# qo-100-lora-transceiver.net
KiCad netlist of a schematic drawn in EAGLE
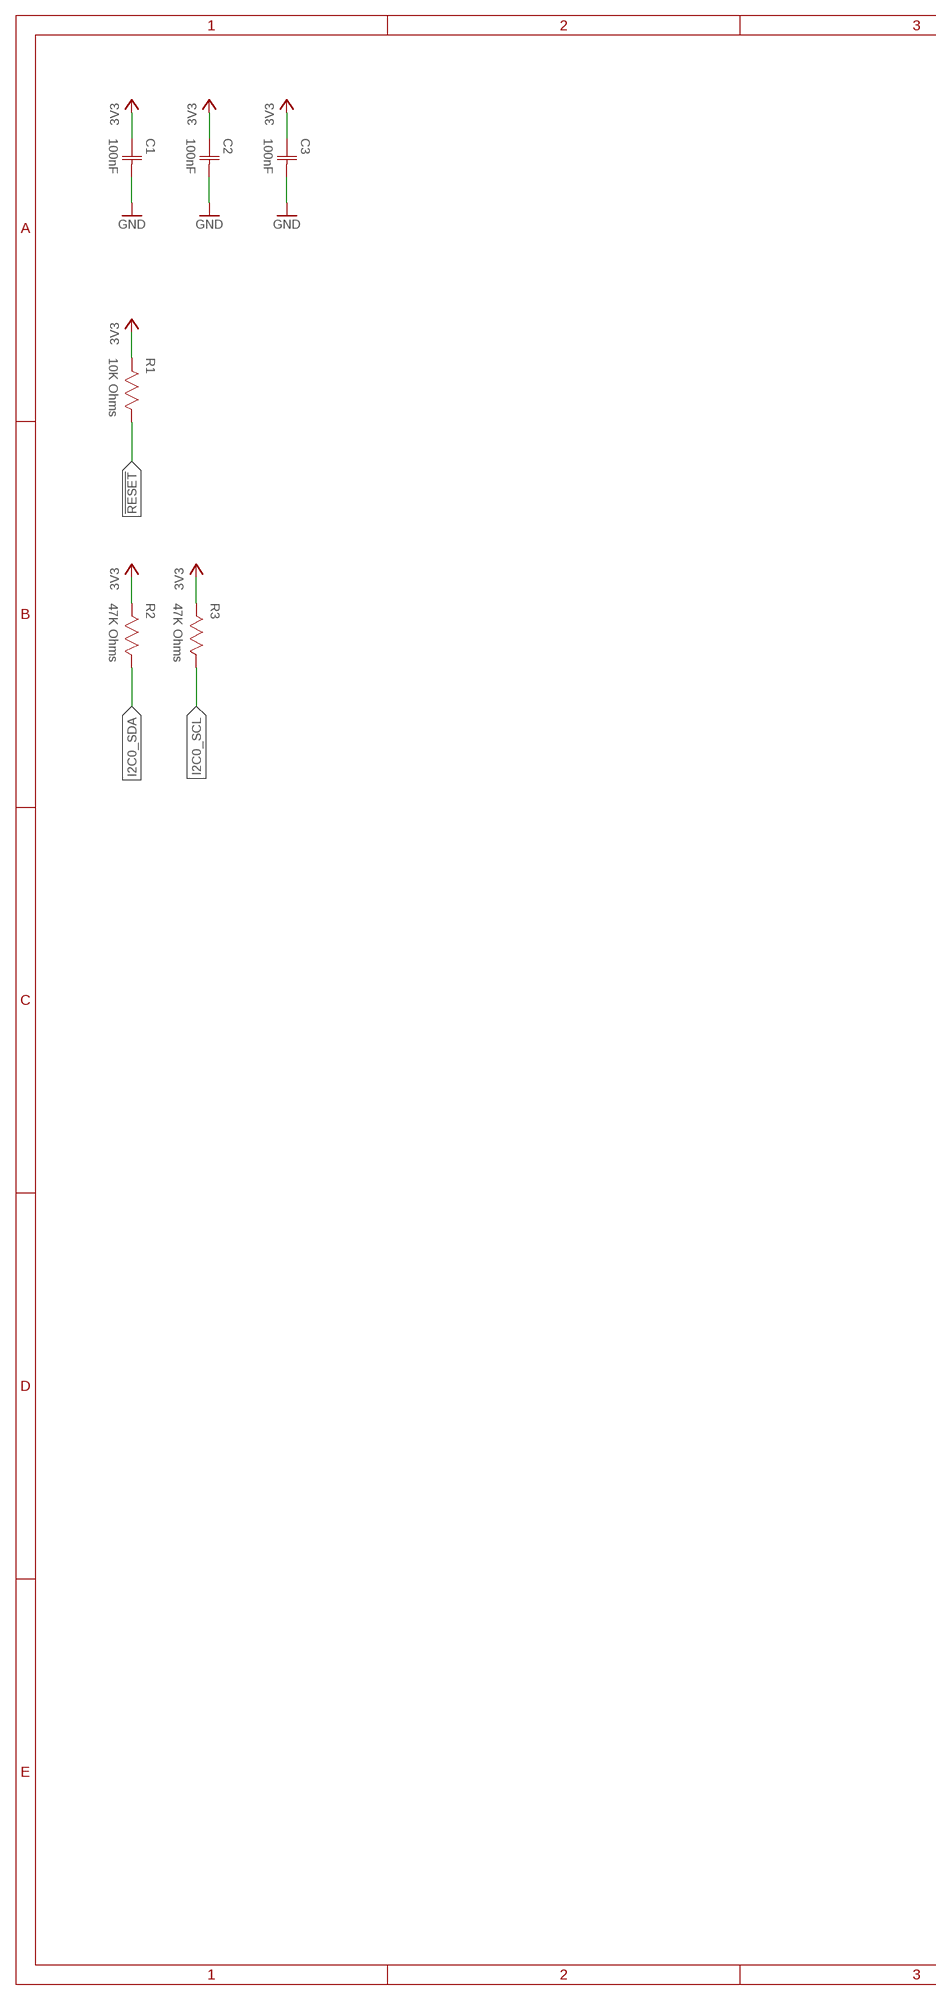
[diagram p0: schematic, sheet 1, part 1 of 2]
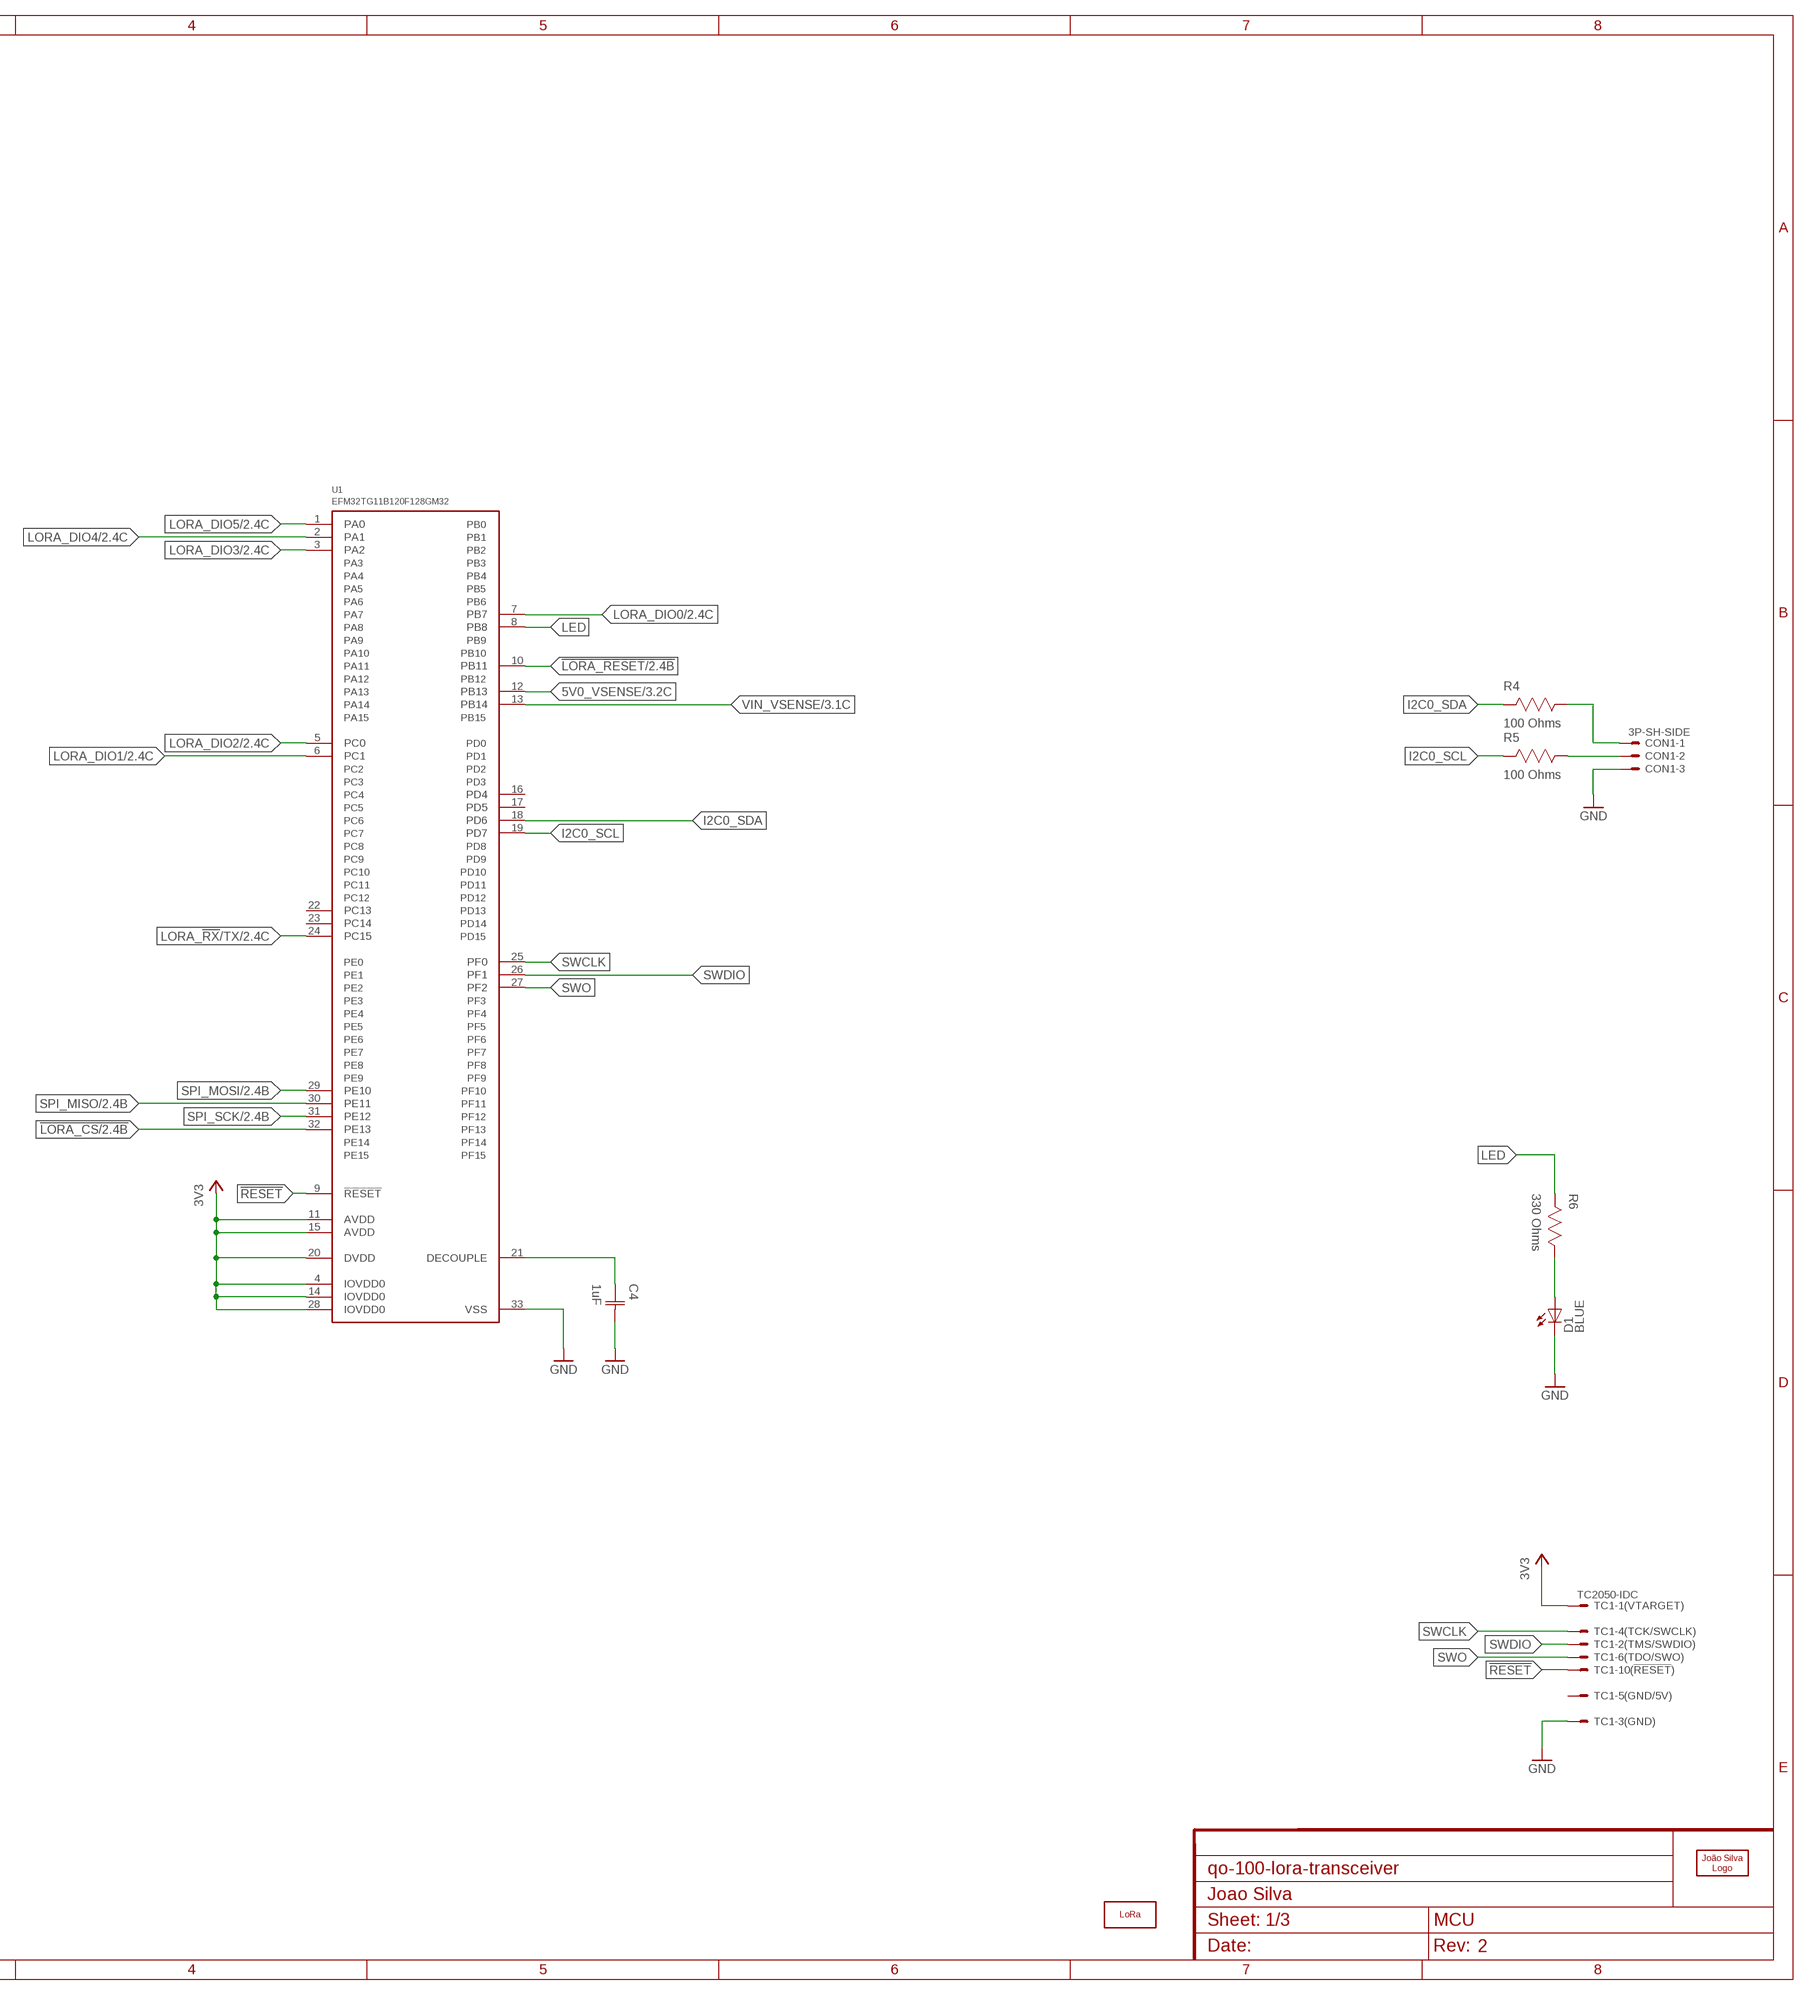
[diagram p1: schematic, sheet 1, part 2 of 2]
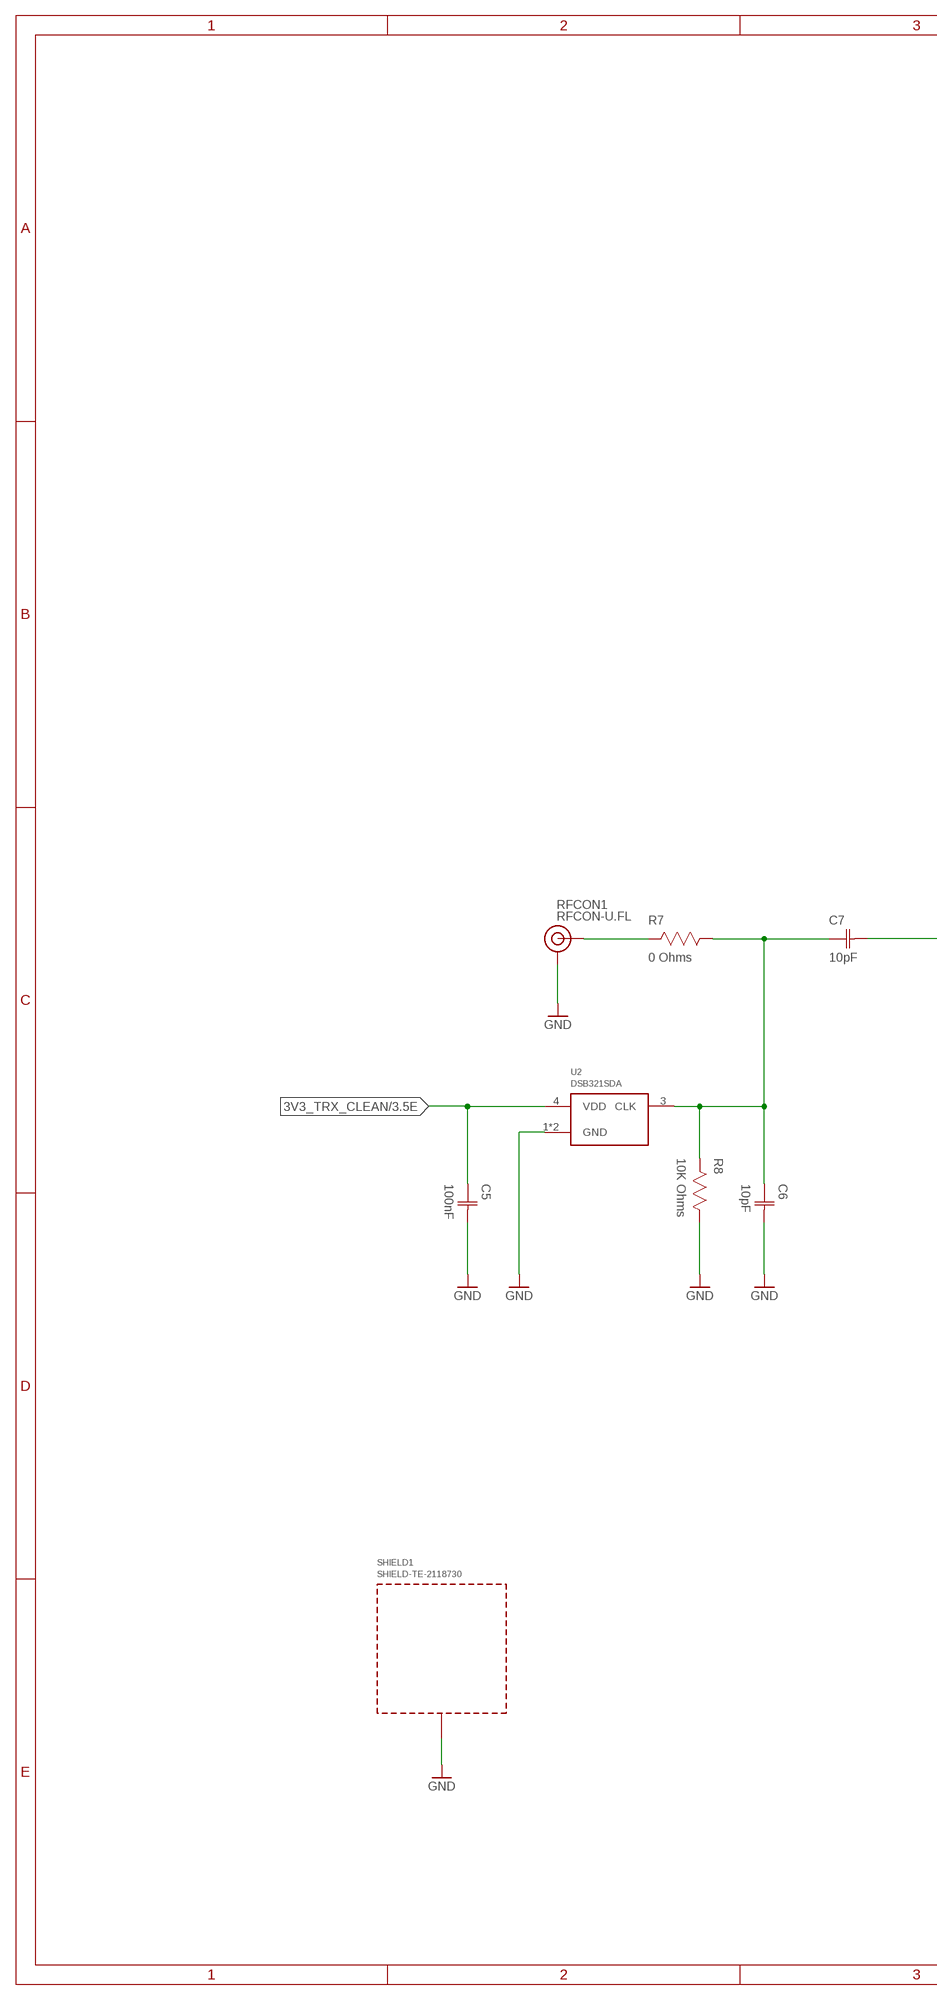
[diagram p2: schematic, sheet 2, part 1 of 2]
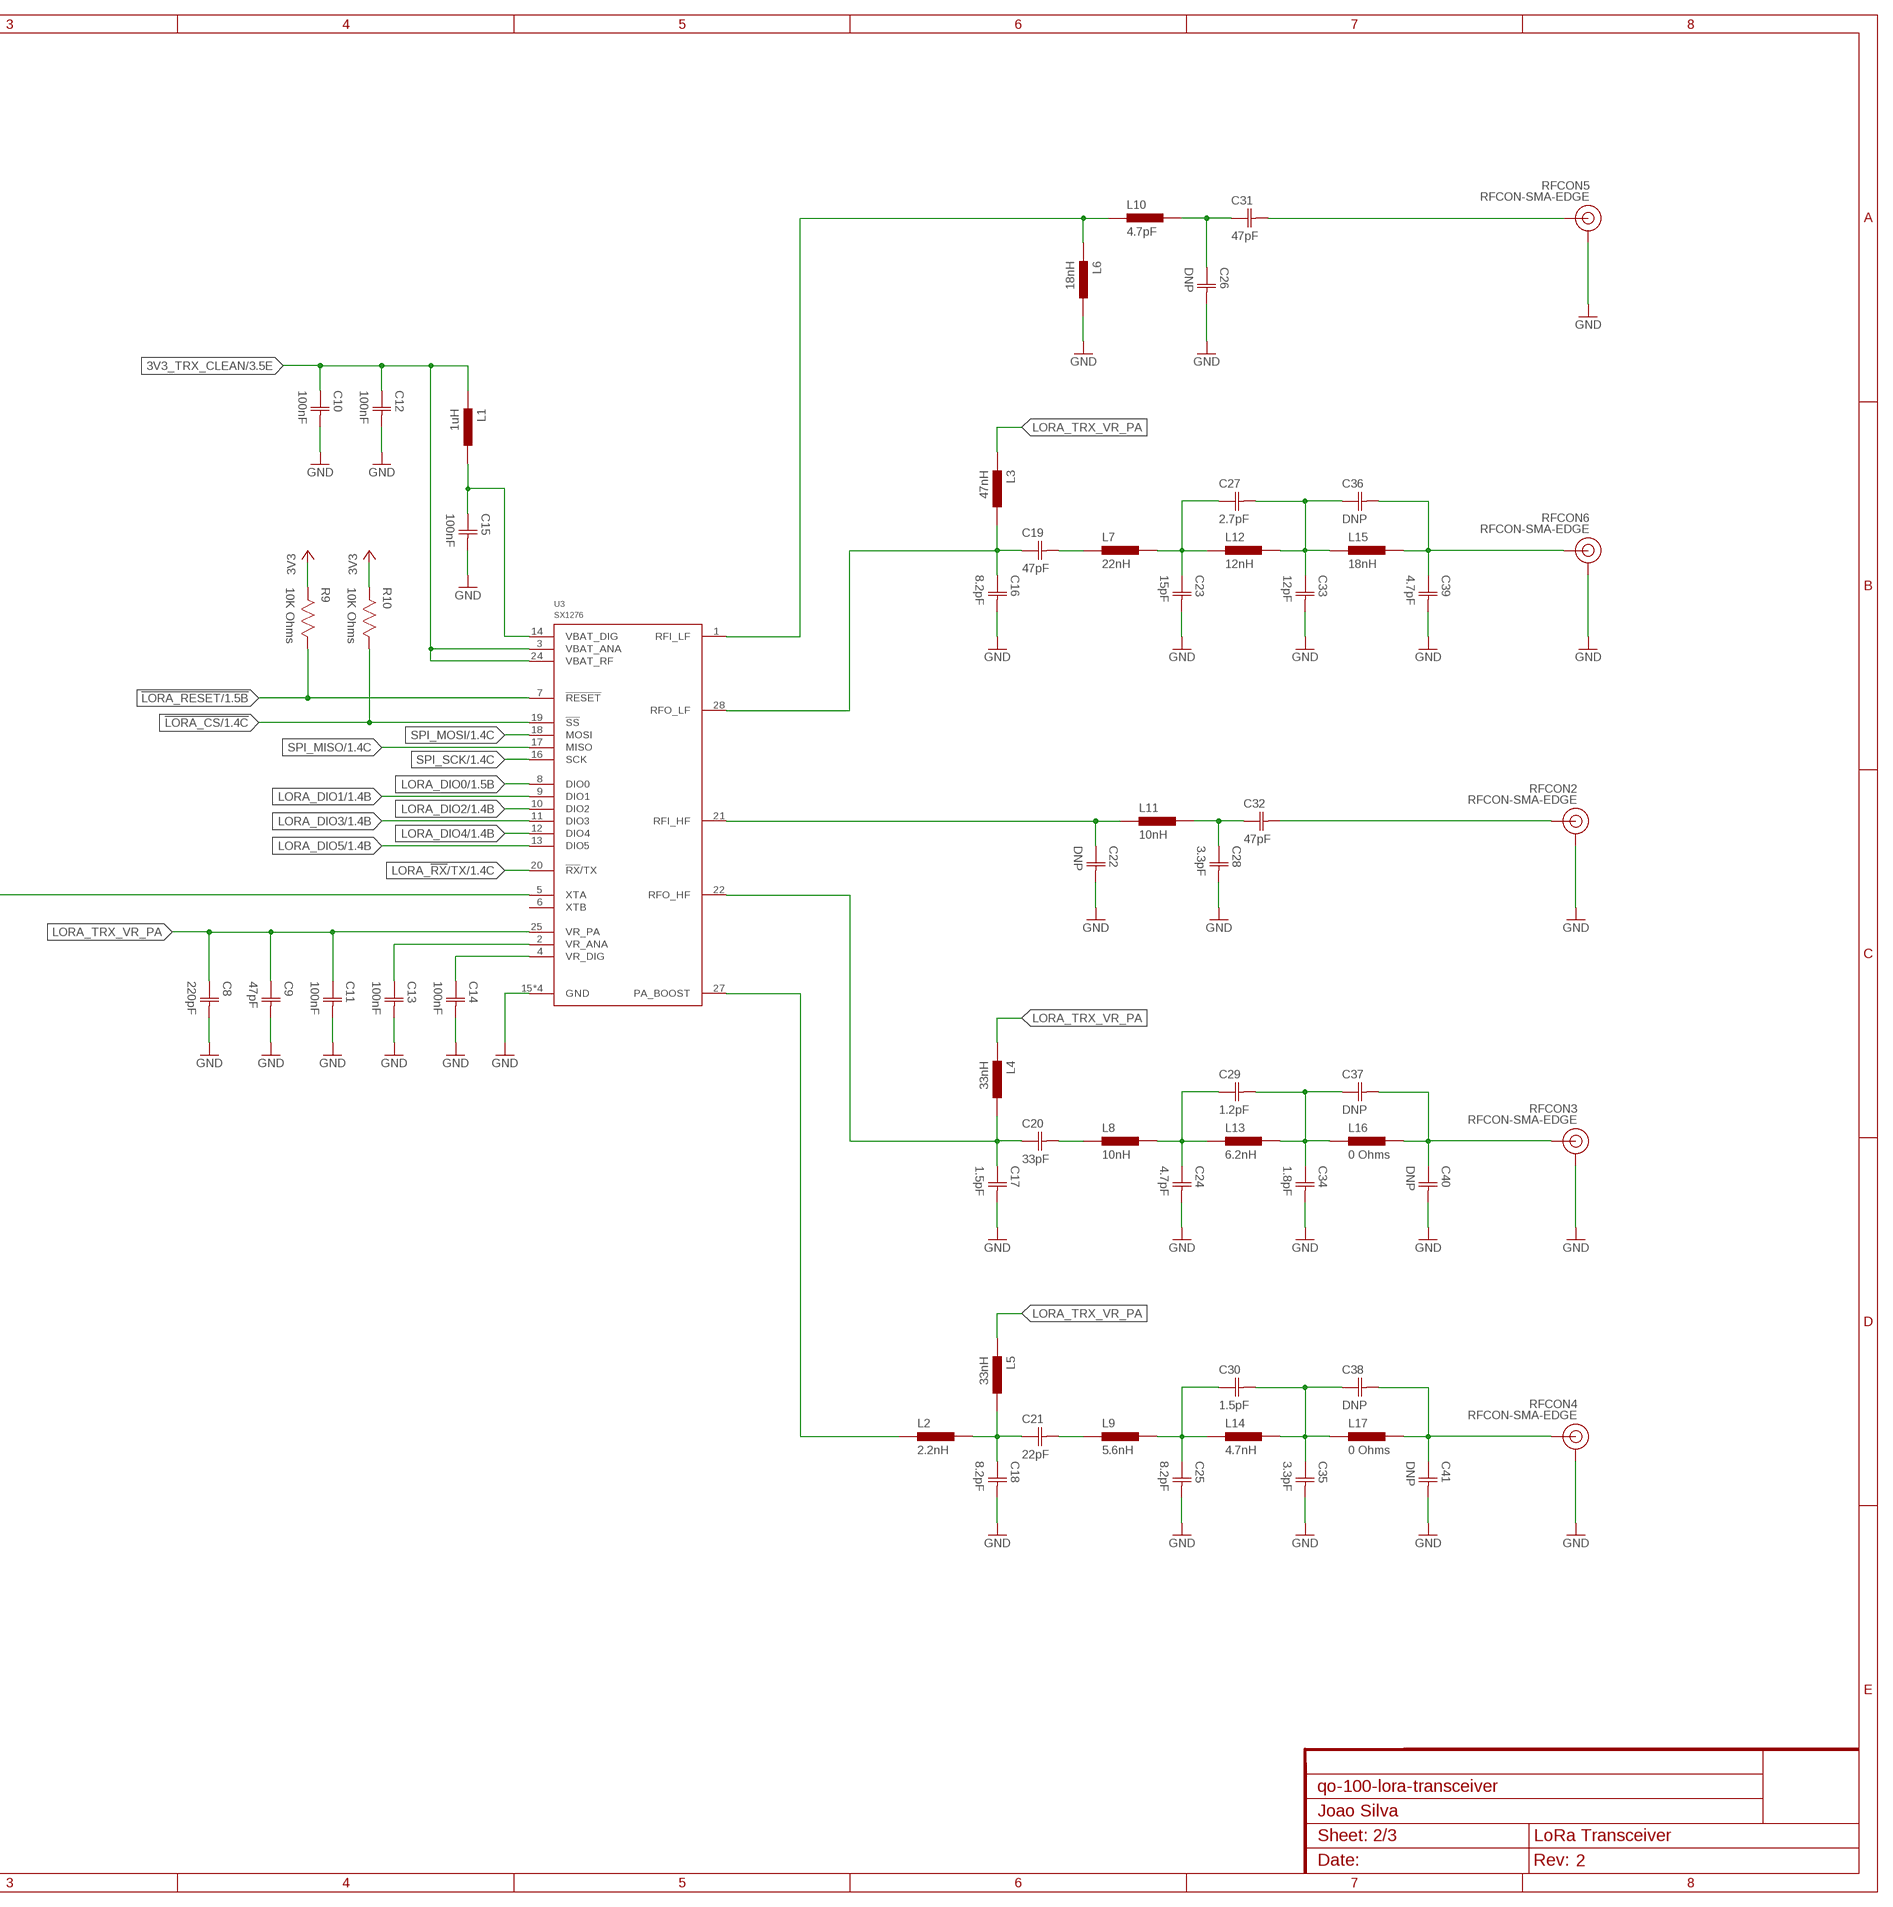
[diagram p3: schematic, sheet 2, part 2 of 2]
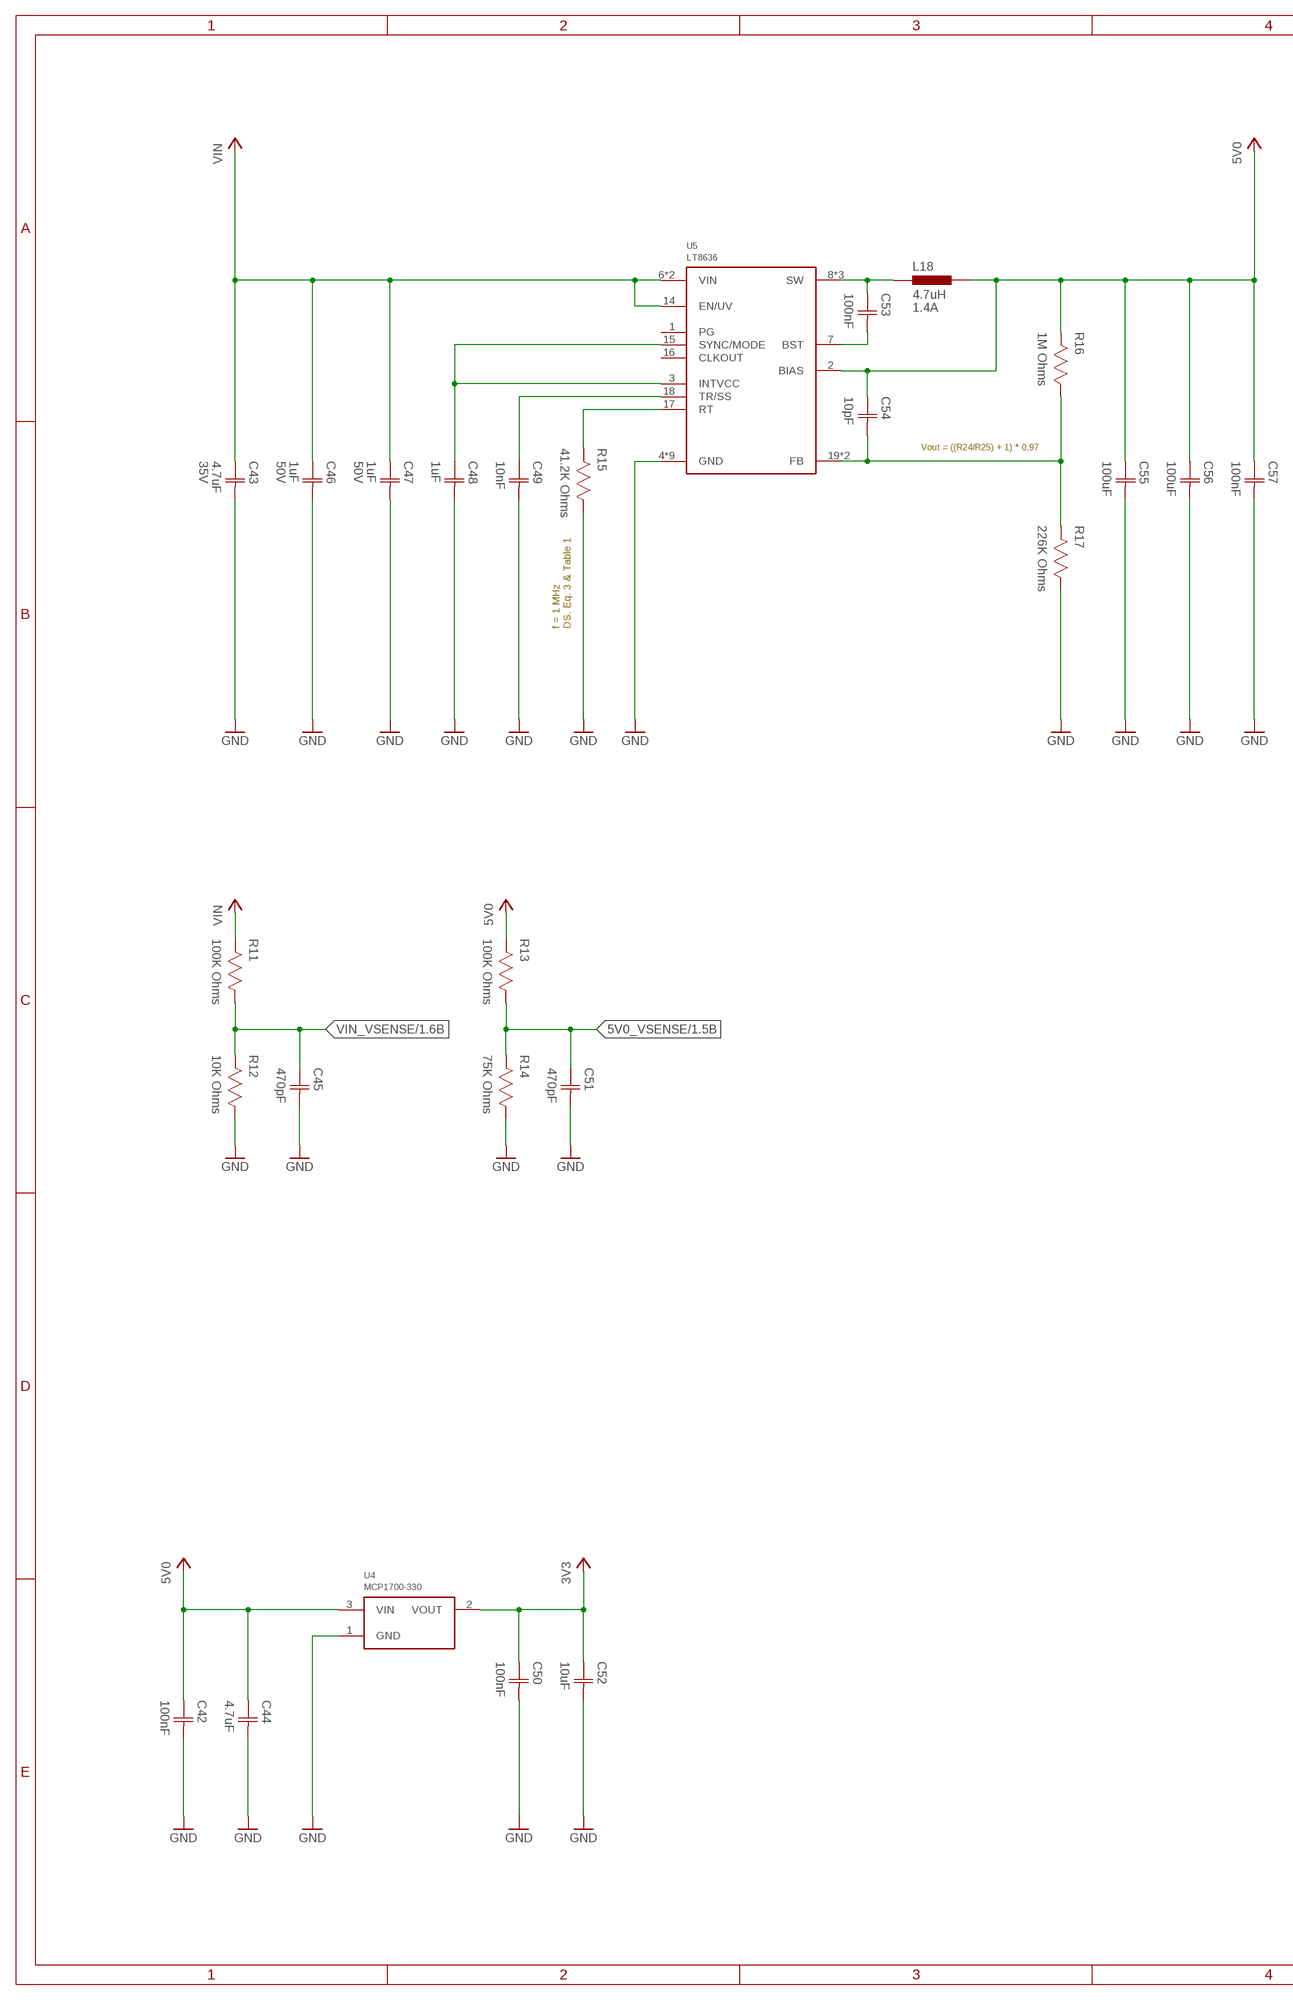
[diagram p4: schematic, sheet 3, part 1 of 2]
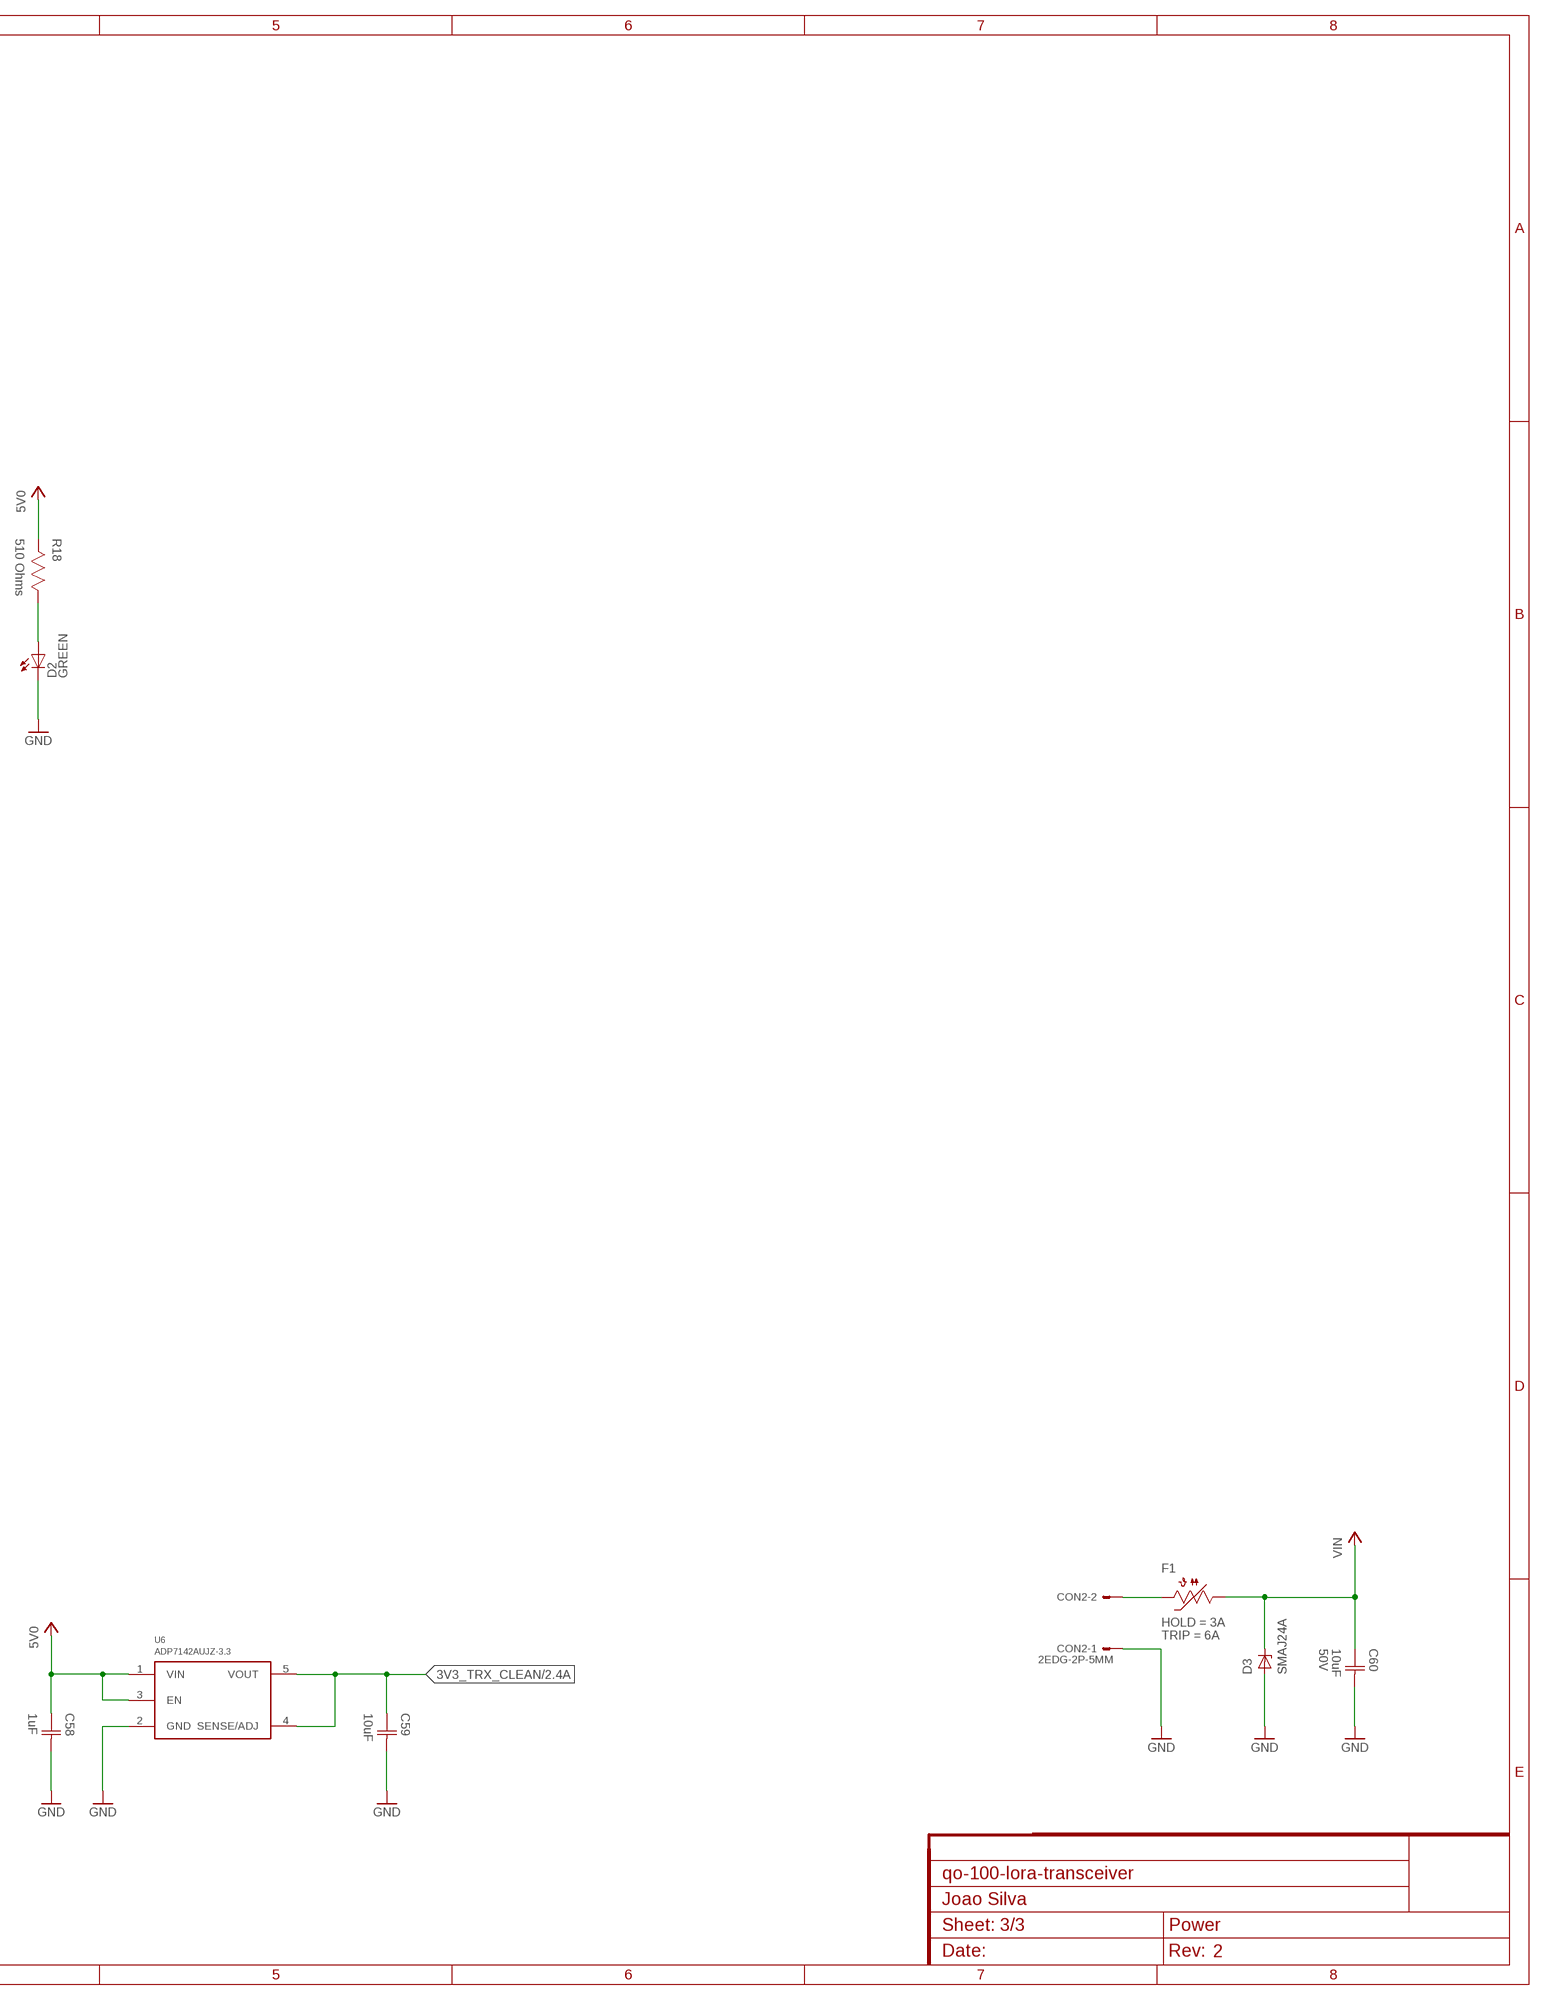
[diagram p5: schematic, sheet 3, part 2 of 2]

(export (version "E")
  (design (tool "Eeschema 10.0.6"))
  (components
    (comp (ref "C5")
      (value "100nF")
      (footprint "eagle-import:CAP0603")
      (libsource (lib "eagle-import") (part "CAPACITOR-0603"))
    )
    (comp (ref "C6")
      (value "10pF")
      (footprint "eagle-import:CAP0603")
      (libsource (lib "eagle-import") (part "CAPACITOR-0603"))
    )
    (comp (ref "C7")
      (value "10pF")
      (footprint "eagle-import:CAP0603")
      (libsource (lib "eagle-import") (part "CAPACITOR-0603"))
    )
    (comp (ref "C8")
      (value "220pF")
      (footprint "eagle-import:CAP0603")
      (libsource (lib "eagle-import") (part "CAPACITOR-0603"))
    )
    (comp (ref "C9")
      (value "47pF")
      (footprint "eagle-import:CAP0603")
      (libsource (lib "eagle-import") (part "CAPACITOR-0603"))
    )
    (comp (ref "C10")
      (value "100nF")
      (footprint "eagle-import:CAP0603")
      (libsource (lib "eagle-import") (part "CAPACITOR-0603"))
    )
    (comp (ref "C11")
      (value "100nF")
      (footprint "eagle-import:CAP0603")
      (libsource (lib "eagle-import") (part "CAPACITOR-0603"))
    )
    (comp (ref "C12")
      (value "100nF")
      (footprint "eagle-import:CAP0603")
      (libsource (lib "eagle-import") (part "CAPACITOR-0603"))
    )
    (comp (ref "C13")
      (value "100nF")
      (footprint "eagle-import:CAP0603")
      (libsource (lib "eagle-import") (part "CAPACITOR-0603"))
    )
    (comp (ref "C14")
      (value "100nF")
      (footprint "eagle-import:CAP0603")
      (libsource (lib "eagle-import") (part "CAPACITOR-0603"))
    )
    (comp (ref "C15")
      (value "100nF")
      (footprint "eagle-import:CAP0603")
      (libsource (lib "eagle-import") (part "CAPACITOR-0603"))
    )
    (comp (ref "C16")
      (value "8.2pF")
      (footprint "eagle-import:CAP0603")
      (libsource (lib "eagle-import") (part "CAPACITOR-0603"))
    )
    (comp (ref "C17")
      (value "1.5pF")
      (footprint "eagle-import:CAP0603")
      (libsource (lib "eagle-import") (part "CAPACITOR-0603"))
    )
    (comp (ref "C18")
      (value "8.2pF")
      (footprint "eagle-import:CAP0603")
      (libsource (lib "eagle-import") (part "CAPACITOR-0603"))
    )
    (comp (ref "C19")
      (value "47pF")
      (footprint "eagle-import:CAP0603")
      (libsource (lib "eagle-import") (part "CAPACITOR-0603"))
    )
    (comp (ref "C20")
      (value "33pF")
      (footprint "eagle-import:CAP0603")
      (libsource (lib "eagle-import") (part "CAPACITOR-0603"))
    )
    (comp (ref "C21")
      (value "22pF")
      (footprint "eagle-import:CAP0603")
      (libsource (lib "eagle-import") (part "CAPACITOR-0603"))
    )
    (comp (ref "C22")
      (value "DNP")
      (footprint "eagle-import:CAP0603")
      (libsource (lib "eagle-import") (part "CAPACITOR-0603"))
    )
    (comp (ref "C23")
      (value "15pF")
      (footprint "eagle-import:CAP0603")
      (libsource (lib "eagle-import") (part "CAPACITOR-0603"))
    )
    (comp (ref "C24")
      (value "4.7pF")
      (footprint "eagle-import:CAP0603")
      (libsource (lib "eagle-import") (part "CAPACITOR-0603"))
    )
    (comp (ref "C25")
      (value "8.2pF")
      (footprint "eagle-import:CAP0603")
      (libsource (lib "eagle-import") (part "CAPACITOR-0603"))
    )
    (comp (ref "C26")
      (value "DNP")
      (footprint "eagle-import:CAP0603")
      (libsource (lib "eagle-import") (part "CAPACITOR-0603"))
    )
    (comp (ref "C27")
      (value "2.7pF")
      (footprint "eagle-import:CAP0603")
      (libsource (lib "eagle-import") (part "CAPACITOR-0603"))
    )
    (comp (ref "C28")
      (value "3.3pF")
      (footprint "eagle-import:CAP0603")
      (libsource (lib "eagle-import") (part "CAPACITOR-0603"))
    )
    (comp (ref "C29")
      (value "1.2pF")
      (footprint "eagle-import:CAP0603")
      (libsource (lib "eagle-import") (part "CAPACITOR-0603"))
    )
    (comp (ref "C30")
      (value "1.5pF")
      (footprint "eagle-import:CAP0603")
      (libsource (lib "eagle-import") (part "CAPACITOR-0603"))
    )
    (comp (ref "C31")
      (value "47pF")
      (footprint "eagle-import:CAP0603")
      (libsource (lib "eagle-import") (part "CAPACITOR-0603"))
    )
    (comp (ref "C32")
      (value "47pF")
      (footprint "eagle-import:CAP0603")
      (libsource (lib "eagle-import") (part "CAPACITOR-0603"))
    )
    (comp (ref "C33")
      (value "12pF")
      (footprint "eagle-import:CAP0603")
      (libsource (lib "eagle-import") (part "CAPACITOR-0603"))
    )
    (comp (ref "C34")
      (value "1.8pF")
      (footprint "eagle-import:CAP0603")
      (libsource (lib "eagle-import") (part "CAPACITOR-0603"))
    )
    (comp (ref "C35")
      (value "3.3pF")
      (footprint "eagle-import:CAP0603")
      (libsource (lib "eagle-import") (part "CAPACITOR-0603"))
    )
    (comp (ref "C36")
      (value "DNP")
      (footprint "eagle-import:CAP0603")
      (libsource (lib "eagle-import") (part "CAPACITOR-0603"))
    )
    (comp (ref "C37")
      (value "DNP")
      (footprint "eagle-import:CAP0603")
      (libsource (lib "eagle-import") (part "CAPACITOR-0603"))
    )
    (comp (ref "C38")
      (value "DNP")
      (footprint "eagle-import:CAP0603")
      (libsource (lib "eagle-import") (part "CAPACITOR-0603"))
    )
    (comp (ref "C39")
      (value "4.7pF")
      (footprint "eagle-import:CAP0603")
      (libsource (lib "eagle-import") (part "CAPACITOR-0603"))
    )
    (comp (ref "C40")
      (value "DNP")
      (footprint "eagle-import:CAP0603")
      (libsource (lib "eagle-import") (part "CAPACITOR-0603"))
    )
    (comp (ref "C41")
      (value "DNP")
      (footprint "eagle-import:CAP0603")
      (libsource (lib "eagle-import") (part "CAPACITOR-0603"))
    )
    (comp (ref "L1")
      (value "1uH")
      (footprint "eagle-import:IND0603")
      (libsource (lib "eagle-import") (part "INDUCTOR-0603"))
    )
    (comp (ref "L2")
      (value "2.2nH")
      (footprint "eagle-import:IND0603")
      (libsource (lib "eagle-import") (part "INDUCTOR-0603"))
    )
    (comp (ref "L3")
      (value "47nH")
      (footprint "eagle-import:IND0603")
      (libsource (lib "eagle-import") (part "INDUCTOR-0603"))
    )
    (comp (ref "L4")
      (value "33nH")
      (footprint "eagle-import:IND0603")
      (libsource (lib "eagle-import") (part "INDUCTOR-0603"))
    )
    (comp (ref "L5")
      (value "33nH")
      (footprint "eagle-import:IND0603")
      (libsource (lib "eagle-import") (part "INDUCTOR-0603"))
    )
    (comp (ref "L6")
      (value "18nH")
      (footprint "eagle-import:IND0603")
      (libsource (lib "eagle-import") (part "INDUCTOR-0603"))
    )
    (comp (ref "L7")
      (value "22nH")
      (footprint "eagle-import:IND0603")
      (libsource (lib "eagle-import") (part "INDUCTOR-0603"))
    )
    (comp (ref "L8")
      (value "10nH")
      (footprint "eagle-import:IND0603")
      (libsource (lib "eagle-import") (part "INDUCTOR-0603"))
    )
    (comp (ref "L9")
      (value "5.6nH")
      (footprint "eagle-import:IND0603")
      (libsource (lib "eagle-import") (part "INDUCTOR-0603"))
    )
    (comp (ref "L10")
      (value "4.7pF")
      (footprint "eagle-import:IND0603")
      (libsource (lib "eagle-import") (part "INDUCTOR-0603"))
    )
    (comp (ref "L11")
      (value "10nH")
      (footprint "eagle-import:IND0603")
      (libsource (lib "eagle-import") (part "INDUCTOR-0603"))
    )
    (comp (ref "L12")
      (value "12nH")
      (footprint "eagle-import:IND0603")
      (libsource (lib "eagle-import") (part "INDUCTOR-0603"))
    )
    (comp (ref "L13")
      (value "6.2nH")
      (footprint "eagle-import:IND0603")
      (libsource (lib "eagle-import") (part "INDUCTOR-0603"))
    )
    (comp (ref "L14")
      (value "4.7nH")
      (footprint "eagle-import:IND0603")
      (libsource (lib "eagle-import") (part "INDUCTOR-0603"))
    )
    (comp (ref "L15")
      (value "18nH")
      (footprint "eagle-import:IND0603")
      (libsource (lib "eagle-import") (part "INDUCTOR-0603"))
    )
    (comp (ref "L16")
      (value "0 Ohms")
      (footprint "eagle-import:IND0603")
      (libsource (lib "eagle-import") (part "INDUCTOR-0603"))
    )
    (comp (ref "L17")
      (value "0 Ohms")
      (footprint "eagle-import:IND0603")
      (libsource (lib "eagle-import") (part "INDUCTOR-0603"))
    )
    (comp (ref "R7")
      (value "0 Ohms")
      (footprint "eagle-import:RES0603")
      (libsource (lib "eagle-import") (part "RESISTOR-0603"))
    )
    (comp (ref "R8")
      (value "10K Ohms")
      (footprint "eagle-import:RES0603")
      (libsource (lib "eagle-import") (part "RESISTOR-0603"))
    )
    (comp (ref "R9")
      (value "10K Ohms")
      (footprint "eagle-import:RES0603")
      (libsource (lib "eagle-import") (part "RESISTOR-0603"))
    )
    (comp (ref "R10")
      (value "10K Ohms")
      (footprint "eagle-import:RES0603")
      (libsource (lib "eagle-import") (part "RESISTOR-0603"))
    )
    (comp (ref "RFCON1")
      (value "RFCON-U.FL")
      (footprint "eagle-import:U.FL")
      (libsource (lib "eagle-import") (part "RFCON-U.FL"))
    )
    (comp (ref "RFCON2")
      (value "RFCON-SMA-EDGE")
      (footprint "eagle-import:SMA-EDGE")
      (libsource (lib "eagle-import") (part "RFCON-SMA-EDGE"))
    )
    (comp (ref "RFCON3")
      (value "RFCON-SMA-EDGE")
      (footprint "eagle-import:SMA-EDGE")
      (libsource (lib "eagle-import") (part "RFCON-SMA-EDGE"))
    )
    (comp (ref "RFCON4")
      (value "RFCON-SMA-EDGE")
      (footprint "eagle-import:SMA-EDGE")
      (libsource (lib "eagle-import") (part "RFCON-SMA-EDGE"))
    )
    (comp (ref "RFCON5")
      (value "RFCON-SMA-EDGE")
      (footprint "eagle-import:SMA-EDGE")
      (libsource (lib "eagle-import") (part "RFCON-SMA-EDGE"))
    )
    (comp (ref "RFCON6")
      (value "RFCON-SMA-EDGE")
      (footprint "eagle-import:SMA-EDGE")
      (libsource (lib "eagle-import") (part "RFCON-SMA-EDGE"))
    )
    (comp (ref "SHIELD1")
      (value "SHIELD-TE-2118730")
      (footprint "eagle-import:2118730")
      (libsource (lib "eagle-import") (part "SHIELD-TE-2118730"))
    )
    (comp (ref "U2")
      (value "DSB321SDA")
      (footprint "eagle-import:TCXO-3225")
      (libsource (lib "eagle-import") (part "DSB321SDA"))
    )
    (comp (ref "U3")
      (value "SX1276")
      (footprint "eagle-import:QFN28")
      (libsource (lib "eagle-import") (part "SX1276"))
    )
    (comp (ref "C42")
      (value "100nF")
      (footprint "eagle-import:CAP0603")
      (libsource (lib "eagle-import") (part "CAPACITOR-0603"))
    )
    (comp (ref "C43")
      (value "4.7uF")
      (footprint "eagle-import:CAP0603")
      (fields (field (name "VOLTAGE") "35V"))
      (libsource (lib "eagle-import") (part "CAPACITOR-0603"))
    )
    (comp (ref "C44")
      (value "4.7uF")
      (footprint "eagle-import:CAP0603")
      (libsource (lib "eagle-import") (part "CAPACITOR-0603"))
    )
    (comp (ref "C45")
      (value "470pF")
      (footprint "eagle-import:CAP0603")
      (libsource (lib "eagle-import") (part "CAPACITOR-0603"))
    )
    (comp (ref "C46")
      (value "1uF")
      (footprint "eagle-import:CAP0603")
      (fields (field (name "VOLTAGE") "50V"))
      (libsource (lib "eagle-import") (part "CAPACITOR-0603"))
    )
    (comp (ref "C47")
      (value "1uF")
      (footprint "eagle-import:CAP0603")
      (fields (field (name "VOLTAGE") "50V"))
      (libsource (lib "eagle-import") (part "CAPACITOR-0603"))
    )
    (comp (ref "C48")
      (value "1uF")
      (footprint "eagle-import:CAP0603")
      (libsource (lib "eagle-import") (part "CAPACITOR-0603"))
    )
    (comp (ref "C49")
      (value "10nF")
      (footprint "eagle-import:CAP0603")
      (libsource (lib "eagle-import") (part "CAPACITOR-0603"))
    )
    (comp (ref "C50")
      (value "100nF")
      (footprint "eagle-import:CAP0603")
      (libsource (lib "eagle-import") (part "CAPACITOR-0603"))
    )
    (comp (ref "C51")
      (value "470pF")
      (footprint "eagle-import:CAP0603")
      (libsource (lib "eagle-import") (part "CAPACITOR-0603"))
    )
    (comp (ref "C52")
      (value "10uF")
      (footprint "eagle-import:CAP0603")
      (libsource (lib "eagle-import") (part "CAPACITOR-0603"))
    )
    (comp (ref "C53")
      (value "100nF")
      (footprint "eagle-import:CAP0603")
      (libsource (lib "eagle-import") (part "CAPACITOR-0603"))
    )
    (comp (ref "C54")
      (value "10pF")
      (footprint "eagle-import:CAP0603")
      (libsource (lib "eagle-import") (part "CAPACITOR-0603"))
    )
    (comp (ref "C55")
      (value "100uF")
      (footprint "eagle-import:CAP1206")
      (libsource (lib "eagle-import") (part "CAPACITOR-1206"))
    )
    (comp (ref "C56")
      (value "100uF")
      (footprint "eagle-import:CAP1206")
      (libsource (lib "eagle-import") (part "CAPACITOR-1206"))
    )
    (comp (ref "C57")
      (value "100nF")
      (footprint "eagle-import:CAP0603")
      (libsource (lib "eagle-import") (part "CAPACITOR-0603"))
    )
    (comp (ref "C58")
      (value "1uF")
      (footprint "eagle-import:CAP0603")
      (libsource (lib "eagle-import") (part "CAPACITOR-0603"))
    )
    (comp (ref "C59")
      (value "10uF")
      (footprint "eagle-import:CAP0603")
      (libsource (lib "eagle-import") (part "CAPACITOR-0603"))
    )
    (comp (ref "C60")
      (value "10uF")
      (footprint "eagle-import:CAP1206")
      (fields (field (name "VOLTAGE") "50V"))
      (libsource (lib "eagle-import") (part "CAPACITOR-1206"))
    )
    (comp (ref "CON2")
      (value "2EDG-2P-5MM")
      (footprint "eagle-import:2EDG-2P-5MM")
      (libsource (lib "eagle-import") (part "2EDG-2P-5MM"))
    )
    (comp (ref "D2")
      (value "LED0603")
      (footprint "eagle-import:0603")
      (fields (field (name "COLOR") "GREEN"))
      (libsource (lib "eagle-import") (part "LED0603"))
    )
    (comp (ref "D3")
      (value "SMAJ24A")
      (footprint "eagle-import:DO214AC")
      (fields (field (name "MF") "Littelfuse"))
      (libsource (lib "eagle-import") (part "SMAJA24"))
    )
    (comp (ref "F1")
      (value "2.6A Hold")
      (footprint "eagle-import:1206")
      (fields (field (name "HOLD") "3A") (field (name "TRIP") "6A"))
      (libsource (lib "eagle-import") (part "PTC1206"))
    )
    (comp (ref "L18")
      (value "4.7uH")
      (footprint "eagle-import:IND2520")
      (fields (field (name "CURRENT") "1.4A"))
      (libsource (lib "eagle-import") (part "INDUCTOR-2.5X2X1.2MM"))
    )
    (comp (ref "R11")
      (value "100K Ohms")
      (footprint "eagle-import:RES0603")
      (libsource (lib "eagle-import") (part "RESISTOR-0603"))
    )
    (comp (ref "R12")
      (value "10K Ohms")
      (footprint "eagle-import:RES0603")
      (libsource (lib "eagle-import") (part "RESISTOR-0603"))
    )
    (comp (ref "R13")
      (value "100K Ohms")
      (footprint "eagle-import:RES0603")
      (libsource (lib "eagle-import") (part "RESISTOR-0603"))
    )
    (comp (ref "R14")
      (value "75K Ohms")
      (footprint "eagle-import:RES0603")
      (libsource (lib "eagle-import") (part "RESISTOR-0603"))
    )
    (comp (ref "R15")
      (value "41.2K Ohms")
      (footprint "eagle-import:RES0603")
      (libsource (lib "eagle-import") (part "RESISTOR-0603"))
    )
    (comp (ref "R16")
      (value "1M Ohms")
      (footprint "eagle-import:RES0603")
      (libsource (lib "eagle-import") (part "RESISTOR-0603"))
    )
    (comp (ref "R17")
      (value "226K Ohms")
      (footprint "eagle-import:RES0603")
      (libsource (lib "eagle-import") (part "RESISTOR-0603"))
    )
    (comp (ref "R18")
      (value "510 Ohms")
      (footprint "eagle-import:RES0603")
      (libsource (lib "eagle-import") (part "RESISTOR-0603"))
    )
    (comp (ref "U4")
      (value "MCP1700-330")
      (footprint "eagle-import:SOT23")
      (libsource (lib "eagle-import") (part "MCP1700-330"))
    )
    (comp (ref "U5")
      (value "LT8636")
      (footprint "eagle-import:QFN20_ASYM_CORNER")
      (libsource (lib "eagle-import") (part "LT8636"))
    )
    (comp (ref "U6")
      (value "ADP7142AUJZ-3.3")
      (footprint "eagle-import:SOT23-5")
      (libsource (lib "eagle-import") (part "ADP7142AUJZ-3.3"))
    )
    (comp (ref "C1")
      (value "100nF")
      (footprint "eagle-import:CAP0603")
      (libsource (lib "eagle-import") (part "CAPACITOR-0603"))
    )
    (comp (ref "C2")
      (value "100nF")
      (footprint "eagle-import:CAP0603")
      (libsource (lib "eagle-import") (part "CAPACITOR-0603"))
    )
    (comp (ref "C3")
      (value "100nF")
      (footprint "eagle-import:CAP0603")
      (libsource (lib "eagle-import") (part "CAPACITOR-0603"))
    )
    (comp (ref "C4")
      (value "1uF")
      (footprint "eagle-import:CAP0603")
      (libsource (lib "eagle-import") (part "CAPACITOR-0603"))
    )
    (comp (ref "CON1")
      (value "3P-SH-SIDE")
      (footprint "eagle-import:SH-03-SIDE")
      (libsource (lib "eagle-import") (part "3P-SH-SIDE"))
    )
    (comp (ref "D1")
      (value "LED0603")
      (footprint "eagle-import:0603")
      (fields (field (name "COLOR") "BLUE"))
      (libsource (lib "eagle-import") (part "LED0603"))
    )
    (comp (ref "LOGO1")
      (value "LORA-10MM")
      (footprint "eagle-import:LORA_10MM")
      (libsource (lib "eagle-import") (part "LORA-10MM"))
    )
    (comp (ref "LOGO2")
      (value "JS-10MM")
      (footprint "eagle-import:JS_10MM")
      (libsource (lib "eagle-import") (part "JS-10MM"))
    )
    (comp (ref "R1")
      (value "10K Ohms")
      (footprint "eagle-import:RES0603")
      (libsource (lib "eagle-import") (part "RESISTOR-0603"))
    )
    (comp (ref "R2")
      (value "47K Ohms")
      (footprint "eagle-import:RES0603")
      (libsource (lib "eagle-import") (part "RESISTOR-0603"))
    )
    (comp (ref "R3")
      (value "47K Ohms")
      (footprint "eagle-import:RES0603")
      (libsource (lib "eagle-import") (part "RESISTOR-0603"))
    )
    (comp (ref "R4")
      (value "100 Ohms")
      (footprint "eagle-import:RES0603")
      (libsource (lib "eagle-import") (part "RESISTOR-0603"))
    )
    (comp (ref "R5")
      (value "100 Ohms")
      (footprint "eagle-import:RES0603")
      (libsource (lib "eagle-import") (part "RESISTOR-0603"))
    )
    (comp (ref "R6")
      (value "330 Ohms")
      (footprint "eagle-import:RES0603")
      (libsource (lib "eagle-import") (part "RESISTOR-0603"))
    )
    (comp (ref "TC1")
      (value "TC2050-IDC")
      (footprint "eagle-import:TC2050-IDC")
      (libsource (lib "eagle-import") (part "TC2050-IDC"))
    )
    (comp (ref "U1")
      (value "EFM32TG11B120F128GM32")
      (footprint "eagle-import:QFN32_0.5P_TG")
      (libsource (lib "eagle-import") (part "EFM32TG11B1M3220F128G"))
    )
  )
  (nets
    (net (code "1") (name "3V3") (class "Default")
      (node (ref "C1") (pin "1") (pinfunction "C1_1") (pintype "passive"))
      (node (ref "C2") (pin "1") (pinfunction "C1_1") (pintype "passive"))
      (node (ref "C3") (pin "1") (pinfunction "C1_1") (pintype "passive"))
      (node (ref "C50") (pin "1") (pinfunction "C1_1") (pintype "passive"))
      (node (ref "C52") (pin "1") (pinfunction "C1_1") (pintype "passive"))
      (node (ref "R1") (pin "2") (pinfunction "2_2") (pintype "passive"))
      (node (ref "R10") (pin "2") (pinfunction "2_2") (pintype "passive"))
      (node (ref "R2") (pin "2") (pinfunction "2_2") (pintype "passive"))
      (node (ref "R3") (pin "2") (pinfunction "2_2") (pintype "passive"))
      (node (ref "R9") (pin "2") (pinfunction "2_2") (pintype "passive"))
      (node (ref "TC1") (pin "1") (pinfunction "S_1") (pintype "passive"))
      (node (ref "U1") (pin "11") (pinfunction "AVDD_11") (pintype "bidirectional"))
      (node (ref "U1") (pin "14") (pinfunction "IOVDD0_14") (pintype "bidirectional"))
      (node (ref "U1") (pin "15") (pinfunction "AVDD_15") (pintype "bidirectional"))
      (node (ref "U1") (pin "20") (pinfunction "DVDD_20") (pintype "bidirectional"))
      (node (ref "U1") (pin "28") (pinfunction "IOVDD0_28") (pintype "bidirectional"))
      (node (ref "U1") (pin "4") (pinfunction "IOVDD0_4") (pintype "bidirectional"))
      (node (ref "U4") (pin "2") (pinfunction "VOUT_2") (pintype "bidirectional"))
    )
    (net (code "2") (name "3V3_TRX_CLEAN") (class "Default")
      (node (ref "C10") (pin "1") (pinfunction "C1_1") (pintype "passive"))
      (node (ref "C12") (pin "1") (pinfunction "C1_1") (pintype "passive"))
      (node (ref "C5") (pin "1") (pinfunction "C1_1") (pintype "passive"))
      (node (ref "C59") (pin "1") (pinfunction "C1_1") (pintype "passive"))
      (node (ref "L1") (pin "1") (pinfunction "1_1") (pintype "passive"))
      (node (ref "U2") (pin "4") (pinfunction "VDD_4") (pintype "power_in"))
      (node (ref "U3") (pin "24") (pinfunction "VBAT_RF_24") (pintype "bidirectional"))
      (node (ref "U3") (pin "3") (pinfunction "VBAT_ANA_3") (pintype "bidirectional"))
      (node (ref "U6") (pin "4") (pinfunction "SENSE/ADJ_4") (pintype "bidirectional"))
      (node (ref "U6") (pin "5") (pinfunction "VOUT_5") (pintype "bidirectional"))
    )
    (net (code "3") (name "5V0") (class "Default")
      (node (ref "C42") (pin "1") (pinfunction "C1_1") (pintype "passive"))
      (node (ref "C44") (pin "1") (pinfunction "C1_1") (pintype "passive"))
      (node (ref "C54") (pin "1") (pinfunction "C1_1") (pintype "passive"))
      (node (ref "C55") (pin "1") (pinfunction "C1_1") (pintype "passive"))
      (node (ref "C56") (pin "1") (pinfunction "C1_1") (pintype "passive"))
      (node (ref "C57") (pin "1") (pinfunction "C1_1") (pintype "passive"))
      (node (ref "C58") (pin "1") (pinfunction "C1_1") (pintype "passive"))
      (node (ref "L18") (pin "2") (pinfunction "2_2") (pintype "passive"))
      (node (ref "R13") (pin "2") (pinfunction "2_2") (pintype "passive"))
      (node (ref "R16") (pin "2") (pinfunction "2_2") (pintype "passive"))
      (node (ref "R18") (pin "2") (pinfunction "2_2") (pintype "passive"))
      (node (ref "U4") (pin "3") (pinfunction "VIN_3") (pintype "bidirectional"))
      (node (ref "U5") (pin "2") (pinfunction "BIAS_2") (pintype "bidirectional"))
      (node (ref "U6") (pin "1") (pinfunction "VIN_1") (pintype "bidirectional"))
      (node (ref "U6") (pin "3") (pinfunction "EN_3") (pintype "bidirectional"))
    )
    (net (code "4") (name "5V0_VSENSE") (class "Default")
      (node (ref "C51") (pin "1") (pinfunction "C1_1") (pintype "passive"))
      (node (ref "R13") (pin "1") (pinfunction "1_1") (pintype "passive"))
      (node (ref "R14") (pin "2") (pinfunction "2_2") (pintype "passive"))
      (node (ref "U1") (pin "12") (pinfunction "PB13_12") (pintype "bidirectional"))
    )
    (net (code "5") (name "GND") (class "Default")
      (node (ref "C1") (pin "2") (pinfunction "C2_2") (pintype "passive"))
      (node (ref "C10") (pin "2") (pinfunction "C2_2") (pintype "passive"))
      (node (ref "C11") (pin "2") (pinfunction "C2_2") (pintype "passive"))
      (node (ref "C12") (pin "2") (pinfunction "C2_2") (pintype "passive"))
      (node (ref "C13") (pin "2") (pinfunction "C2_2") (pintype "passive"))
      (node (ref "C14") (pin "2") (pinfunction "C2_2") (pintype "passive"))
      (node (ref "C15") (pin "2") (pinfunction "C2_2") (pintype "passive"))
      (node (ref "C16") (pin "2") (pinfunction "C2_2") (pintype "passive"))
      (node (ref "C17") (pin "2") (pinfunction "C2_2") (pintype "passive"))
      (node (ref "C18") (pin "2") (pinfunction "C2_2") (pintype "passive"))
      (node (ref "C2") (pin "2") (pinfunction "C2_2") (pintype "passive"))
      (node (ref "C22") (pin "2") (pinfunction "C2_2") (pintype "passive"))
      (node (ref "C23") (pin "2") (pinfunction "C2_2") (pintype "passive"))
      (node (ref "C24") (pin "2") (pinfunction "C2_2") (pintype "passive"))
      (node (ref "C25") (pin "2") (pinfunction "C2_2") (pintype "passive"))
      (node (ref "C26") (pin "2") (pinfunction "C2_2") (pintype "passive"))
      (node (ref "C28") (pin "2") (pinfunction "C2_2") (pintype "passive"))
      (node (ref "C3") (pin "2") (pinfunction "C2_2") (pintype "passive"))
      (node (ref "C33") (pin "2") (pinfunction "C2_2") (pintype "passive"))
      (node (ref "C34") (pin "2") (pinfunction "C2_2") (pintype "passive"))
      (node (ref "C35") (pin "2") (pinfunction "C2_2") (pintype "passive"))
      (node (ref "C39") (pin "2") (pinfunction "C2_2") (pintype "passive"))
      (node (ref "C4") (pin "2") (pinfunction "C2_2") (pintype "passive"))
      (node (ref "C40") (pin "2") (pinfunction "C2_2") (pintype "passive"))
      (node (ref "C41") (pin "2") (pinfunction "C2_2") (pintype "passive"))
      (node (ref "C42") (pin "2") (pinfunction "C2_2") (pintype "passive"))
      (node (ref "C43") (pin "2") (pinfunction "C2_2") (pintype "passive"))
      (node (ref "C44") (pin "2") (pinfunction "C2_2") (pintype "passive"))
      (node (ref "C45") (pin "2") (pinfunction "C2_2") (pintype "passive"))
      (node (ref "C46") (pin "2") (pinfunction "C2_2") (pintype "passive"))
      (node (ref "C47") (pin "2") (pinfunction "C2_2") (pintype "passive"))
      (node (ref "C48") (pin "2") (pinfunction "C2_2") (pintype "passive"))
      (node (ref "C49") (pin "2") (pinfunction "C2_2") (pintype "passive"))
      (node (ref "C5") (pin "2") (pinfunction "C2_2") (pintype "passive"))
      (node (ref "C50") (pin "2") (pinfunction "C2_2") (pintype "passive"))
      (node (ref "C51") (pin "2") (pinfunction "C2_2") (pintype "passive"))
      (node (ref "C52") (pin "2") (pinfunction "C2_2") (pintype "passive"))
      (node (ref "C55") (pin "2") (pinfunction "C2_2") (pintype "passive"))
      (node (ref "C56") (pin "2") (pinfunction "C2_2") (pintype "passive"))
      (node (ref "C57") (pin "2") (pinfunction "C2_2") (pintype "passive"))
      (node (ref "C58") (pin "2") (pinfunction "C2_2") (pintype "passive"))
      (node (ref "C59") (pin "2") (pinfunction "C2_2") (pintype "passive"))
      (node (ref "C6") (pin "2") (pinfunction "C2_2") (pintype "passive"))
      (node (ref "C60") (pin "2") (pinfunction "C2_2") (pintype "passive"))
      (node (ref "C8") (pin "2") (pinfunction "C2_2") (pintype "passive"))
      (node (ref "C9") (pin "2") (pinfunction "C2_2") (pintype "passive"))
      (node (ref "CON1") (pin "3") (pinfunction "S_3") (pintype "passive"))
      (node (ref "CON2") (pin "P$1") (pinfunction "S_P$1") (pintype "passive"))
      (node (ref "D1") (pin "C") (pinfunction "C_C") (pintype "passive"))
      (node (ref "D2") (pin "C") (pinfunction "C_C") (pintype "passive"))
      (node (ref "D3") (pin "A") (pinfunction "A_A") (pintype "passive"))
      (node (ref "L6") (pin "2") (pinfunction "2_2") (pintype "passive"))
      (node (ref "R12") (pin "1") (pinfunction "1_1") (pintype "passive"))
      (node (ref "R14") (pin "1") (pinfunction "1_1") (pintype "passive"))
      (node (ref "R15") (pin "1") (pinfunction "1_1") (pintype "passive"))
      (node (ref "R17") (pin "1") (pinfunction "1_1") (pintype "passive"))
      (node (ref "R8") (pin "1") (pinfunction "1_1") (pintype "passive"))
      (node (ref "RFCON1") (pin "P$1") (pinfunction "GND_P$1") (pintype "bidirectional"))
      (node (ref "RFCON1") (pin "P$2") (pinfunction "GND_P$2") (pintype "bidirectional"))
      (node (ref "RFCON2") (pin "GND@0") (pinfunction "GND_GND@0") (pintype "bidirectional"))
      (node (ref "RFCON2") (pin "GND@1") (pinfunction "GND_GND@1") (pintype "bidirectional"))
      (node (ref "RFCON2") (pin "GND@2") (pinfunction "GND_GND@2") (pintype "bidirectional"))
      (node (ref "RFCON2") (pin "GND@3") (pinfunction "GND_GND@3") (pintype "bidirectional"))
      (node (ref "RFCON3") (pin "GND@0") (pinfunction "GND_GND@0") (pintype "bidirectional"))
      (node (ref "RFCON3") (pin "GND@1") (pinfunction "GND_GND@1") (pintype "bidirectional"))
      (node (ref "RFCON3") (pin "GND@2") (pinfunction "GND_GND@2") (pintype "bidirectional"))
      (node (ref "RFCON3") (pin "GND@3") (pinfunction "GND_GND@3") (pintype "bidirectional"))
      (node (ref "RFCON4") (pin "GND@0") (pinfunction "GND_GND@0") (pintype "bidirectional"))
      (node (ref "RFCON4") (pin "GND@1") (pinfunction "GND_GND@1") (pintype "bidirectional"))
      (node (ref "RFCON4") (pin "GND@2") (pinfunction "GND_GND@2") (pintype "bidirectional"))
      (node (ref "RFCON4") (pin "GND@3") (pinfunction "GND_GND@3") (pintype "bidirectional"))
      (node (ref "RFCON5") (pin "GND@0") (pinfunction "GND_GND@0") (pintype "bidirectional"))
      (node (ref "RFCON5") (pin "GND@1") (pinfunction "GND_GND@1") (pintype "bidirectional"))
      (node (ref "RFCON5") (pin "GND@2") (pinfunction "GND_GND@2") (pintype "bidirectional"))
      (node (ref "RFCON5") (pin "GND@3") (pinfunction "GND_GND@3") (pintype "bidirectional"))
      (node (ref "RFCON6") (pin "GND@0") (pinfunction "GND_GND@0") (pintype "bidirectional"))
      (node (ref "RFCON6") (pin "GND@1") (pinfunction "GND_GND@1") (pintype "bidirectional"))
      (node (ref "RFCON6") (pin "GND@2") (pinfunction "GND_GND@2") (pintype "bidirectional"))
      (node (ref "RFCON6") (pin "GND@3") (pinfunction "GND_GND@3") (pintype "bidirectional"))
      (node (ref "SHIELD1") (pin "1") (pinfunction "GND_1") (pintype "bidirectional"))
      (node (ref "SHIELD1") (pin "10") (pinfunction "GND_10") (pintype "bidirectional"))
      (node (ref "SHIELD1") (pin "11") (pinfunction "GND_11") (pintype "bidirectional"))
      (node (ref "SHIELD1") (pin "12") (pinfunction "GND_12") (pintype "bidirectional"))
      (node (ref "SHIELD1") (pin "13") (pinfunction "GND_13") (pintype "bidirectional"))
      (node (ref "SHIELD1") (pin "14") (pinfunction "GND_14") (pintype "bidirectional"))
      (node (ref "SHIELD1") (pin "15") (pinfunction "GND_15") (pintype "bidirectional"))
      (node (ref "SHIELD1") (pin "16") (pinfunction "GND_16") (pintype "bidirectional"))
      (node (ref "SHIELD1") (pin "17") (pinfunction "GND_17") (pintype "bidirectional"))
      (node (ref "SHIELD1") (pin "18") (pinfunction "GND_18") (pintype "bidirectional"))
      (node (ref "SHIELD1") (pin "19") (pinfunction "GND_19") (pintype "bidirectional"))
      (node (ref "SHIELD1") (pin "2") (pinfunction "GND_2") (pintype "bidirectional"))
      (node (ref "SHIELD1") (pin "20") (pinfunction "GND_20") (pintype "bidirectional"))
      (node (ref "SHIELD1") (pin "21") (pinfunction "GND_21") (pintype "bidirectional"))
      (node (ref "SHIELD1") (pin "22") (pinfunction "GND_22") (pintype "bidirectional"))
      (node (ref "SHIELD1") (pin "23") (pinfunction "GND_23") (pintype "bidirectional"))
      (node (ref "SHIELD1") (pin "24") (pinfunction "GND_24") (pintype "bidirectional"))
      (node (ref "SHIELD1") (pin "25") (pinfunction "GND_25") (pintype "bidirectional"))
      (node (ref "SHIELD1") (pin "26") (pinfunction "GND_26") (pintype "bidirectional"))
      (node (ref "SHIELD1") (pin "27") (pinfunction "GND_27") (pintype "bidirectional"))
      (node (ref "SHIELD1") (pin "28") (pinfunction "GND_28") (pintype "bidirectional"))
      (node (ref "SHIELD1") (pin "3") (pinfunction "GND_3") (pintype "bidirectional"))
      (node (ref "SHIELD1") (pin "4") (pinfunction "GND_4") (pintype "bidirectional"))
      (node (ref "SHIELD1") (pin "5") (pinfunction "GND_5") (pintype "bidirectional"))
      (node (ref "SHIELD1") (pin "6") (pinfunction "GND_6") (pintype "bidirectional"))
      (node (ref "SHIELD1") (pin "7") (pinfunction "GND_7") (pintype "bidirectional"))
      (node (ref "SHIELD1") (pin "8") (pinfunction "GND_8") (pintype "bidirectional"))
      (node (ref "SHIELD1") (pin "9") (pinfunction "GND_9") (pintype "bidirectional"))
      (node (ref "TC1") (pin "3") (pinfunction "S_3") (pintype "passive"))
      (node (ref "U1") (pin "33") (pinfunction "VSS_33") (pintype "bidirectional"))
      (node (ref "U2") (pin "1") (pinfunction "GND_1") (pintype "power_in"))
      (node (ref "U2") (pin "2") (pinfunction "GND_2") (pintype "power_in"))
      (node (ref "U3") (pin "15") (pinfunction "GND_15") (pintype "bidirectional"))
      (node (ref "U3") (pin "23") (pinfunction "GND_23") (pintype "bidirectional"))
      (node (ref "U3") (pin "26") (pinfunction "GND_26") (pintype "bidirectional"))
      (node (ref "U3") (pin "29") (pinfunction "GND_29") (pintype "bidirectional"))
      (node (ref "U4") (pin "1") (pinfunction "GND_1") (pintype "bidirectional"))
      (node (ref "U5") (pin "12") (pinfunction "GND_12") (pintype "bidirectional"))
      (node (ref "U5") (pin "13") (pinfunction "GND_13") (pintype "bidirectional"))
      (node (ref "U5") (pin "21") (pinfunction "GND_21") (pintype "bidirectional"))
      (node (ref "U5") (pin "4") (pinfunction "GND_4") (pintype "bidirectional"))
      (node (ref "U5") (pin "5") (pinfunction "GND_5") (pintype "bidirectional"))
      (node (ref "U5") (pin "M1") (pinfunction "GND_M1") (pintype "bidirectional"))
      (node (ref "U5") (pin "M2") (pinfunction "GND_M2") (pintype "bidirectional"))
      (node (ref "U5") (pin "M3") (pinfunction "GND_M3") (pintype "bidirectional"))
      (node (ref "U5") (pin "M4") (pinfunction "GND_M4") (pintype "bidirectional"))
      (node (ref "U6") (pin "2") (pinfunction "GND_2") (pintype "bidirectional"))
    )
    (net (code "6") (name "I2C0_SCL") (class "Default")
      (node (ref "R3") (pin "1") (pinfunction "1_1") (pintype "passive"))
      (node (ref "R5") (pin "2") (pinfunction "2_2") (pintype "passive"))
      (node (ref "U1") (pin "19") (pinfunction "PD7_19") (pintype "bidirectional"))
    )
    (net (code "7") (name "I2C0_SDA") (class "Default")
      (node (ref "R2") (pin "1") (pinfunction "1_1") (pintype "passive"))
      (node (ref "R4") (pin "2") (pinfunction "2_2") (pintype "passive"))
      (node (ref "U1") (pin "18") (pinfunction "PD6_18") (pintype "bidirectional"))
    )
    (net (code "8") (name "LED") (class "Default")
      (node (ref "R6") (pin "2") (pinfunction "2_2") (pintype "passive"))
      (node (ref "U1") (pin "8") (pinfunction "PB8_8") (pintype "bidirectional"))
    )
    (net (code "9") (name "LORA_DIO0") (class "Default")
      (node (ref "U1") (pin "7") (pinfunction "PB7_7") (pintype "bidirectional"))
      (node (ref "U3") (pin "8") (pinfunction "DIO0_8") (pintype "bidirectional"))
    )
    (net (code "10") (name "LORA_DIO1") (class "Default")
      (node (ref "U1") (pin "6") (pinfunction "PC1_6") (pintype "bidirectional"))
      (node (ref "U3") (pin "9") (pinfunction "DIO1_9") (pintype "bidirectional"))
    )
    (net (code "11") (name "LORA_DIO2") (class "Default")
      (node (ref "U1") (pin "5") (pinfunction "PC0_5") (pintype "bidirectional"))
      (node (ref "U3") (pin "10") (pinfunction "DIO2_10") (pintype "bidirectional"))
    )
    (net (code "12") (name "LORA_DIO3") (class "Default")
      (node (ref "U1") (pin "3") (pinfunction "PA2_3") (pintype "bidirectional"))
      (node (ref "U3") (pin "11") (pinfunction "DIO3_11") (pintype "bidirectional"))
    )
    (net (code "13") (name "LORA_DIO4") (class "Default")
      (node (ref "U1") (pin "2") (pinfunction "PA1_2") (pintype "bidirectional"))
      (node (ref "U3") (pin "12") (pinfunction "DIO4_12") (pintype "bidirectional"))
    )
    (net (code "14") (name "LORA_DIO5") (class "Default")
      (node (ref "U1") (pin "1") (pinfunction "PA0_1") (pintype "bidirectional"))
      (node (ref "U3") (pin "13") (pinfunction "DIO5_13") (pintype "bidirectional"))
    )
    (net (code "15") (name "LORA_TRX_VR_PA") (class "Default")
      (node (ref "C11") (pin "1") (pinfunction "C1_1") (pintype "passive"))
      (node (ref "C8") (pin "1") (pinfunction "C1_1") (pintype "passive"))
      (node (ref "C9") (pin "1") (pinfunction "C1_1") (pintype "passive"))
      (node (ref "L3") (pin "1") (pinfunction "1_1") (pintype "passive"))
      (node (ref "L4") (pin "1") (pinfunction "1_1") (pintype "passive"))
      (node (ref "L5") (pin "1") (pinfunction "1_1") (pintype "passive"))
      (node (ref "U3") (pin "25") (pinfunction "VR_PA_25") (pintype "bidirectional"))
    )
    (net (code "16") (name "LORA_~{RX}{slash}TX") (class "Default")
      (node (ref "U1") (pin "24") (pinfunction "PC15_24") (pintype "bidirectional"))
      (node (ref "U3") (pin "20") (pinfunction "~{RX}/TX_20") (pintype "bidirectional"))
    )
    (net (code "17") (name "Net-(C4-C1)") (class "Default")
      (node (ref "C4") (pin "1") (pinfunction "C1_1") (pintype "passive"))
      (node (ref "U1") (pin "21") (pinfunction "DECOUPLE_21") (pintype "bidirectional"))
    )
    (net (code "18") (name "Net-(C6-C1)") (class "Default")
      (node (ref "C6") (pin "1") (pinfunction "C1_1") (pintype "passive"))
      (node (ref "C7") (pin "1") (pinfunction "C1_1") (pintype "passive"))
      (node (ref "R7") (pin "1") (pinfunction "1_1") (pintype "passive"))
      (node (ref "R8") (pin "2") (pinfunction "2_2") (pintype "passive"))
      (node (ref "U2") (pin "3") (pinfunction "CLK_3") (pintype "output"))
    )
    (net (code "19") (name "Net-(C7-C2)") (class "Default")
      (node (ref "C7") (pin "2") (pinfunction "C2_2") (pintype "passive"))
      (node (ref "U3") (pin "5") (pinfunction "XTA_5") (pintype "bidirectional"))
    )
    (net (code "20") (name "Net-(C13-C1)") (class "Default")
      (node (ref "C13") (pin "1") (pinfunction "C1_1") (pintype "passive"))
      (node (ref "U3") (pin "2") (pinfunction "VR_ANA_2") (pintype "bidirectional"))
    )
    (net (code "21") (name "Net-(C14-C1)") (class "Default")
      (node (ref "C14") (pin "1") (pinfunction "C1_1") (pintype "passive"))
      (node (ref "U3") (pin "4") (pinfunction "VR_DIG_4") (pintype "bidirectional"))
    )
    (net (code "22") (name "Net-(C15-C1)") (class "Default")
      (node (ref "C15") (pin "1") (pinfunction "C1_1") (pintype "passive"))
      (node (ref "L1") (pin "2") (pinfunction "2_2") (pintype "passive"))
      (node (ref "U3") (pin "14") (pinfunction "VBAT_DIG_14") (pintype "bidirectional"))
    )
    (net (code "23") (name "Net-(C16-C1)") (class "Default")
      (node (ref "C16") (pin "1") (pinfunction "C1_1") (pintype "passive"))
      (node (ref "C19") (pin "1") (pinfunction "C1_1") (pintype "passive"))
      (node (ref "L3") (pin "2") (pinfunction "2_2") (pintype "passive"))
      (node (ref "U3") (pin "28") (pinfunction "RFO_LF_28") (pintype "bidirectional"))
    )
    (net (code "24") (name "Net-(C17-C1)") (class "Default")
      (node (ref "C17") (pin "1") (pinfunction "C1_1") (pintype "passive"))
      (node (ref "C20") (pin "1") (pinfunction "C1_1") (pintype "passive"))
      (node (ref "L4") (pin "2") (pinfunction "2_2") (pintype "passive"))
      (node (ref "U3") (pin "22") (pinfunction "RFO_HF_22") (pintype "bidirectional"))
    )
    (net (code "25") (name "Net-(C18-C1)") (class "Default")
      (node (ref "C18") (pin "1") (pinfunction "C1_1") (pintype "passive"))
      (node (ref "C21") (pin "1") (pinfunction "C1_1") (pintype "passive"))
      (node (ref "L2") (pin "2") (pinfunction "2_2") (pintype "passive"))
      (node (ref "L5") (pin "2") (pinfunction "2_2") (pintype "passive"))
    )
    (net (code "26") (name "Net-(C19-C2)") (class "Default")
      (node (ref "C19") (pin "2") (pinfunction "C2_2") (pintype "passive"))
      (node (ref "L7") (pin "1") (pinfunction "1_1") (pintype "passive"))
    )
    (net (code "27") (name "Net-(C20-C2)") (class "Default")
      (node (ref "C20") (pin "2") (pinfunction "C2_2") (pintype "passive"))
      (node (ref "L8") (pin "1") (pinfunction "1_1") (pintype "passive"))
    )
    (net (code "28") (name "Net-(C21-C2)") (class "Default")
      (node (ref "C21") (pin "2") (pinfunction "C2_2") (pintype "passive"))
      (node (ref "L9") (pin "1") (pinfunction "1_1") (pintype "passive"))
    )
    (net (code "29") (name "Net-(C22-C1)") (class "Default")
      (node (ref "C22") (pin "1") (pinfunction "C1_1") (pintype "passive"))
      (node (ref "L11") (pin "1") (pinfunction "1_1") (pintype "passive"))
      (node (ref "U3") (pin "21") (pinfunction "RFI_HF_21") (pintype "bidirectional"))
    )
    (net (code "30") (name "Net-(C23-C1)") (class "Default")
      (node (ref "C23") (pin "1") (pinfunction "C1_1") (pintype "passive"))
      (node (ref "C27") (pin "1") (pinfunction "C1_1") (pintype "passive"))
      (node (ref "L12") (pin "1") (pinfunction "1_1") (pintype "passive"))
      (node (ref "L7") (pin "2") (pinfunction "2_2") (pintype "passive"))
    )
    (net (code "31") (name "Net-(C24-C1)") (class "Default")
      (node (ref "C24") (pin "1") (pinfunction "C1_1") (pintype "passive"))
      (node (ref "C29") (pin "1") (pinfunction "C1_1") (pintype "passive"))
      (node (ref "L13") (pin "1") (pinfunction "1_1") (pintype "passive"))
      (node (ref "L8") (pin "2") (pinfunction "2_2") (pintype "passive"))
    )
    (net (code "32") (name "Net-(C25-C1)") (class "Default")
      (node (ref "C25") (pin "1") (pinfunction "C1_1") (pintype "passive"))
      (node (ref "C30") (pin "1") (pinfunction "C1_1") (pintype "passive"))
      (node (ref "L14") (pin "1") (pinfunction "1_1") (pintype "passive"))
      (node (ref "L9") (pin "2") (pinfunction "2_2") (pintype "passive"))
    )
    (net (code "33") (name "Net-(C26-C1)") (class "Default")
      (node (ref "C26") (pin "1") (pinfunction "C1_1") (pintype "passive"))
      (node (ref "C31") (pin "1") (pinfunction "C1_1") (pintype "passive"))
      (node (ref "L10") (pin "2") (pinfunction "2_2") (pintype "passive"))
    )
    (net (code "34") (name "Net-(C27-C2)") (class "Default")
      (node (ref "C27") (pin "2") (pinfunction "C2_2") (pintype "passive"))
      (node (ref "C33") (pin "1") (pinfunction "C1_1") (pintype "passive"))
      (node (ref "C36") (pin "1") (pinfunction "C1_1") (pintype "passive"))
      (node (ref "L12") (pin "2") (pinfunction "2_2") (pintype "passive"))
      (node (ref "L15") (pin "1") (pinfunction "1_1") (pintype "passive"))
    )
    (net (code "35") (name "Net-(C28-C1)") (class "Default")
      (node (ref "C28") (pin "1") (pinfunction "C1_1") (pintype "passive"))
      (node (ref "C32") (pin "1") (pinfunction "C1_1") (pintype "passive"))
      (node (ref "L11") (pin "2") (pinfunction "2_2") (pintype "passive"))
    )
    (net (code "36") (name "Net-(C29-C2)") (class "Default")
      (node (ref "C29") (pin "2") (pinfunction "C2_2") (pintype "passive"))
      (node (ref "C34") (pin "1") (pinfunction "C1_1") (pintype "passive"))
      (node (ref "C37") (pin "1") (pinfunction "C1_1") (pintype "passive"))
      (node (ref "L13") (pin "2") (pinfunction "2_2") (pintype "passive"))
      (node (ref "L16") (pin "1") (pinfunction "1_1") (pintype "passive"))
    )
    (net (code "37") (name "Net-(C30-C2)") (class "Default")
      (node (ref "C30") (pin "2") (pinfunction "C2_2") (pintype "passive"))
      (node (ref "C35") (pin "1") (pinfunction "C1_1") (pintype "passive"))
      (node (ref "C38") (pin "1") (pinfunction "C1_1") (pintype "passive"))
      (node (ref "L14") (pin "2") (pinfunction "2_2") (pintype "passive"))
      (node (ref "L17") (pin "1") (pinfunction "1_1") (pintype "passive"))
    )
    (net (code "38") (name "Net-(C31-C2)") (class "Default")
      (node (ref "C31") (pin "2") (pinfunction "C2_2") (pintype "passive"))
      (node (ref "RFCON5") (pin "SIG") (pinfunction "SIGNAL_SIG") (pintype "bidirectional"))
    )
    (net (code "39") (name "Net-(C32-C2)") (class "Default")
      (node (ref "C32") (pin "2") (pinfunction "C2_2") (pintype "passive"))
      (node (ref "RFCON2") (pin "SIG") (pinfunction "SIGNAL_SIG") (pintype "bidirectional"))
    )
    (net (code "40") (name "Net-(C36-C2)") (class "Default")
      (node (ref "C36") (pin "2") (pinfunction "C2_2") (pintype "passive"))
      (node (ref "C39") (pin "1") (pinfunction "C1_1") (pintype "passive"))
      (node (ref "L15") (pin "2") (pinfunction "2_2") (pintype "passive"))
      (node (ref "RFCON6") (pin "SIG") (pinfunction "SIGNAL_SIG") (pintype "bidirectional"))
    )
    (net (code "41") (name "Net-(C37-C2)") (class "Default")
      (node (ref "C37") (pin "2") (pinfunction "C2_2") (pintype "passive"))
      (node (ref "C40") (pin "1") (pinfunction "C1_1") (pintype "passive"))
      (node (ref "L16") (pin "2") (pinfunction "2_2") (pintype "passive"))
      (node (ref "RFCON3") (pin "SIG") (pinfunction "SIGNAL_SIG") (pintype "bidirectional"))
    )
    (net (code "42") (name "Net-(C38-C2)") (class "Default")
      (node (ref "C38") (pin "2") (pinfunction "C2_2") (pintype "passive"))
      (node (ref "C41") (pin "1") (pinfunction "C1_1") (pintype "passive"))
      (node (ref "L17") (pin "2") (pinfunction "2_2") (pintype "passive"))
      (node (ref "RFCON4") (pin "SIG") (pinfunction "SIGNAL_SIG") (pintype "bidirectional"))
    )
    (net (code "43") (name "Net-(C48-C1)") (class "Default")
      (node (ref "C48") (pin "1") (pinfunction "C1_1") (pintype "passive"))
      (node (ref "U5") (pin "15") (pinfunction "SYNC/MODE_15") (pintype "bidirectional"))
      (node (ref "U5") (pin "3") (pinfunction "INTVCC_3") (pintype "bidirectional"))
    )
    (net (code "44") (name "Net-(C49-C1)") (class "Default")
      (node (ref "C49") (pin "1") (pinfunction "C1_1") (pintype "passive"))
      (node (ref "U5") (pin "18") (pinfunction "TR/SS_18") (pintype "bidirectional"))
    )
    (net (code "45") (name "Net-(C53-C1)") (class "Default")
      (node (ref "C53") (pin "1") (pinfunction "C1_1") (pintype "passive"))
      (node (ref "L18") (pin "1") (pinfunction "1_1") (pintype "passive"))
      (node (ref "U5") (pin "10") (pinfunction "SW_10") (pintype "bidirectional"))
      (node (ref "U5") (pin "8") (pinfunction "SW_8") (pintype "bidirectional"))
      (node (ref "U5") (pin "9") (pinfunction "SW_9") (pintype "bidirectional"))
    )
    (net (code "46") (name "Net-(C53-C2)") (class "Default")
      (node (ref "C53") (pin "2") (pinfunction "C2_2") (pintype "passive"))
      (node (ref "U5") (pin "7") (pinfunction "BST_7") (pintype "bidirectional"))
    )
    (net (code "47") (name "Net-(C54-C2)") (class "Default")
      (node (ref "C54") (pin "2") (pinfunction "C2_2") (pintype "passive"))
      (node (ref "R16") (pin "1") (pinfunction "1_1") (pintype "passive"))
      (node (ref "R17") (pin "2") (pinfunction "2_2") (pintype "passive"))
      (node (ref "U5") (pin "19") (pinfunction "FB_19") (pintype "bidirectional"))
      (node (ref "U5") (pin "20") (pinfunction "FB_20") (pintype "bidirectional"))
    )
    (net (code "48") (name "Net-(CON1A-S)") (class "Default")
      (node (ref "CON1") (pin "1") (pinfunction "S_1") (pintype "passive"))
      (node (ref "R4") (pin "1") (pinfunction "1_1") (pintype "passive"))
    )
    (net (code "49") (name "Net-(CON1B-S)") (class "Default")
      (node (ref "CON1") (pin "2") (pinfunction "S_2") (pintype "passive"))
      (node (ref "R5") (pin "1") (pinfunction "1_1") (pintype "passive"))
    )
    (net (code "50") (name "Net-(CON2B-S)") (class "Default")
      (node (ref "CON2") (pin "P$2") (pinfunction "S_P$2") (pintype "passive"))
      (node (ref "F1") (pin "2") (pinfunction "2_2") (pintype "passive"))
    )
    (net (code "51") (name "Net-(D1-PadA)") (class "Default")
      (node (ref "D1") (pin "A") (pinfunction "A_A") (pintype "passive"))
      (node (ref "R6") (pin "1") (pinfunction "1_1") (pintype "passive"))
    )
    (net (code "52") (name "Net-(D2-PadA)") (class "Default")
      (node (ref "D2") (pin "A") (pinfunction "A_A") (pintype "passive"))
      (node (ref "R18") (pin "1") (pinfunction "1_1") (pintype "passive"))
    )
    (net (code "53") (name "Net-(RFCON1-SIGNAL)") (class "Default")
      (node (ref "R7") (pin "2") (pinfunction "2_2") (pintype "passive"))
      (node (ref "RFCON1") (pin "P$3") (pinfunction "SIGNAL_P$3") (pintype "bidirectional"))
    )
    (net (code "54") (name "Net-(U3-PA_BOOST)") (class "Default")
      (node (ref "L2") (pin "1") (pinfunction "1_1") (pintype "passive"))
      (node (ref "U3") (pin "27") (pinfunction "PA_BOOST_27") (pintype "bidirectional"))
    )
    (net (code "55") (name "Net-(U3-RFI_LF)") (class "Default")
      (node (ref "L10") (pin "1") (pinfunction "1_1") (pintype "passive"))
      (node (ref "L6") (pin "1") (pinfunction "1_1") (pintype "passive"))
      (node (ref "U3") (pin "1") (pinfunction "RFI_LF_1") (pintype "bidirectional"))
    )
    (net (code "56") (name "Net-(U5-RT)") (class "Default")
      (node (ref "R15") (pin "2") (pinfunction "2_2") (pintype "passive"))
      (node (ref "U5") (pin "17") (pinfunction "RT_17") (pintype "bidirectional"))
    )
    (net (code "57") (name "SPI_MISO") (class "Default")
      (node (ref "U1") (pin "30") (pinfunction "PE11_30") (pintype "bidirectional"))
      (node (ref "U3") (pin "17") (pinfunction "MISO_17") (pintype "bidirectional"))
    )
    (net (code "58") (name "SPI_MOSI") (class "Default")
      (node (ref "U1") (pin "29") (pinfunction "PE10_29") (pintype "bidirectional"))
      (node (ref "U3") (pin "18") (pinfunction "MOSI_18") (pintype "bidirectional"))
    )
    (net (code "59") (name "SPI_SCK") (class "Default")
      (node (ref "U1") (pin "31") (pinfunction "PE12_31") (pintype "bidirectional"))
      (node (ref "U3") (pin "16") (pinfunction "SCK_16") (pintype "bidirectional"))
    )
    (net (code "60") (name "SWCLK") (class "Default")
      (node (ref "TC1") (pin "4") (pinfunction "S_4") (pintype "passive"))
      (node (ref "U1") (pin "25") (pinfunction "PF0_25") (pintype "bidirectional"))
    )
    (net (code "61") (name "SWDIO") (class "Default")
      (node (ref "TC1") (pin "2") (pinfunction "S_2") (pintype "passive"))
      (node (ref "U1") (pin "26") (pinfunction "PF1_26") (pintype "bidirectional"))
    )
    (net (code "62") (name "SWO") (class "Default")
      (node (ref "TC1") (pin "6") (pinfunction "S_6") (pintype "passive"))
      (node (ref "U1") (pin "27") (pinfunction "PF2_27") (pintype "bidirectional"))
    )
    (net (code "63") (name "VIN") (class "Default")
      (node (ref "C43") (pin "1") (pinfunction "C1_1") (pintype "passive"))
      (node (ref "C46") (pin "1") (pinfunction "C1_1") (pintype "passive"))
      (node (ref "C47") (pin "1") (pinfunction "C1_1") (pintype "passive"))
      (node (ref "C60") (pin "1") (pinfunction "C1_1") (pintype "passive"))
      (node (ref "D3") (pin "C") (pinfunction "C_C") (pintype "passive"))
      (node (ref "F1") (pin "1") (pinfunction "1_1") (pintype "passive"))
      (node (ref "R11") (pin "2") (pinfunction "2_2") (pintype "passive"))
      (node (ref "U5") (pin "11") (pinfunction "VIN_11") (pintype "bidirectional"))
      (node (ref "U5") (pin "14") (pinfunction "EN/UV_14") (pintype "bidirectional"))
      (node (ref "U5") (pin "6") (pinfunction "VIN_6") (pintype "bidirectional"))
    )
    (net (code "64") (name "VIN_VSENSE") (class "Default")
      (node (ref "C45") (pin "1") (pinfunction "C1_1") (pintype "passive"))
      (node (ref "R11") (pin "1") (pinfunction "1_1") (pintype "passive"))
      (node (ref "R12") (pin "2") (pinfunction "2_2") (pintype "passive"))
      (node (ref "U1") (pin "13") (pinfunction "PB14_13") (pintype "bidirectional"))
    )
    (net (code "65") (name "unconnected-(TC1F-S-Pad5)") (class "Default")
      (node (ref "TC1") (pin "5") (pinfunction "S_5") (pintype "passive"))
    )
    (net (code "66") (name "unconnected-(U1-PC13-Pad22)") (class "Default")
      (node (ref "U1") (pin "22") (pinfunction "PC13_22") (pintype "bidirectional"))
    )
    (net (code "67") (name "unconnected-(U1-PC14-Pad23)") (class "Default")
      (node (ref "U1") (pin "23") (pinfunction "PC14_23") (pintype "bidirectional"))
    )
    (net (code "68") (name "unconnected-(U1-PD4-Pad16)") (class "Default")
      (node (ref "U1") (pin "16") (pinfunction "PD4_16") (pintype "bidirectional"))
    )
    (net (code "69") (name "unconnected-(U1-PD5-Pad17)") (class "Default")
      (node (ref "U1") (pin "17") (pinfunction "PD5_17") (pintype "bidirectional"))
    )
    (net (code "70") (name "unconnected-(U3-XTB-Pad6)") (class "Default")
      (node (ref "U3") (pin "6") (pinfunction "XTB_6") (pintype "bidirectional"))
    )
    (net (code "71") (name "unconnected-(U5-CLKOUT-Pad16)") (class "Default")
      (node (ref "U5") (pin "16") (pinfunction "CLKOUT_16") (pintype "bidirectional"))
    )
    (net (code "72") (name "unconnected-(U5-PG-Pad1)") (class "Default")
      (node (ref "U5") (pin "1") (pinfunction "PG_1") (pintype "bidirectional"))
    )
    (net (code "73") (name "~{LORA_CS}") (class "Default")
      (node (ref "R10") (pin "1") (pinfunction "1_1") (pintype "passive"))
      (node (ref "U1") (pin "32") (pinfunction "PE13_32") (pintype "bidirectional"))
      (node (ref "U3") (pin "19") (pinfunction "~{SS}_19") (pintype "bidirectional"))
    )
    (net (code "74") (name "~{LORA_RESET}") (class "Default")
      (node (ref "R9") (pin "1") (pinfunction "1_1") (pintype "passive"))
      (node (ref "U1") (pin "10") (pinfunction "PB11_10") (pintype "bidirectional"))
      (node (ref "U3") (pin "7") (pinfunction "~{RESET}_7") (pintype "bidirectional"))
    )
    (net (code "75") (name "~{RESET}") (class "Default")
      (node (ref "R1") (pin "1") (pinfunction "1_1") (pintype "passive"))
      (node (ref "TC1") (pin "10") (pinfunction "S_10") (pintype "passive"))
      (node (ref "U1") (pin "9") (pinfunction "~{RESET}_9") (pintype "bidirectional"))
    )
  )
)
